# KickerBoard.net
KiCad netlist of a schematic drawn in EAGLE
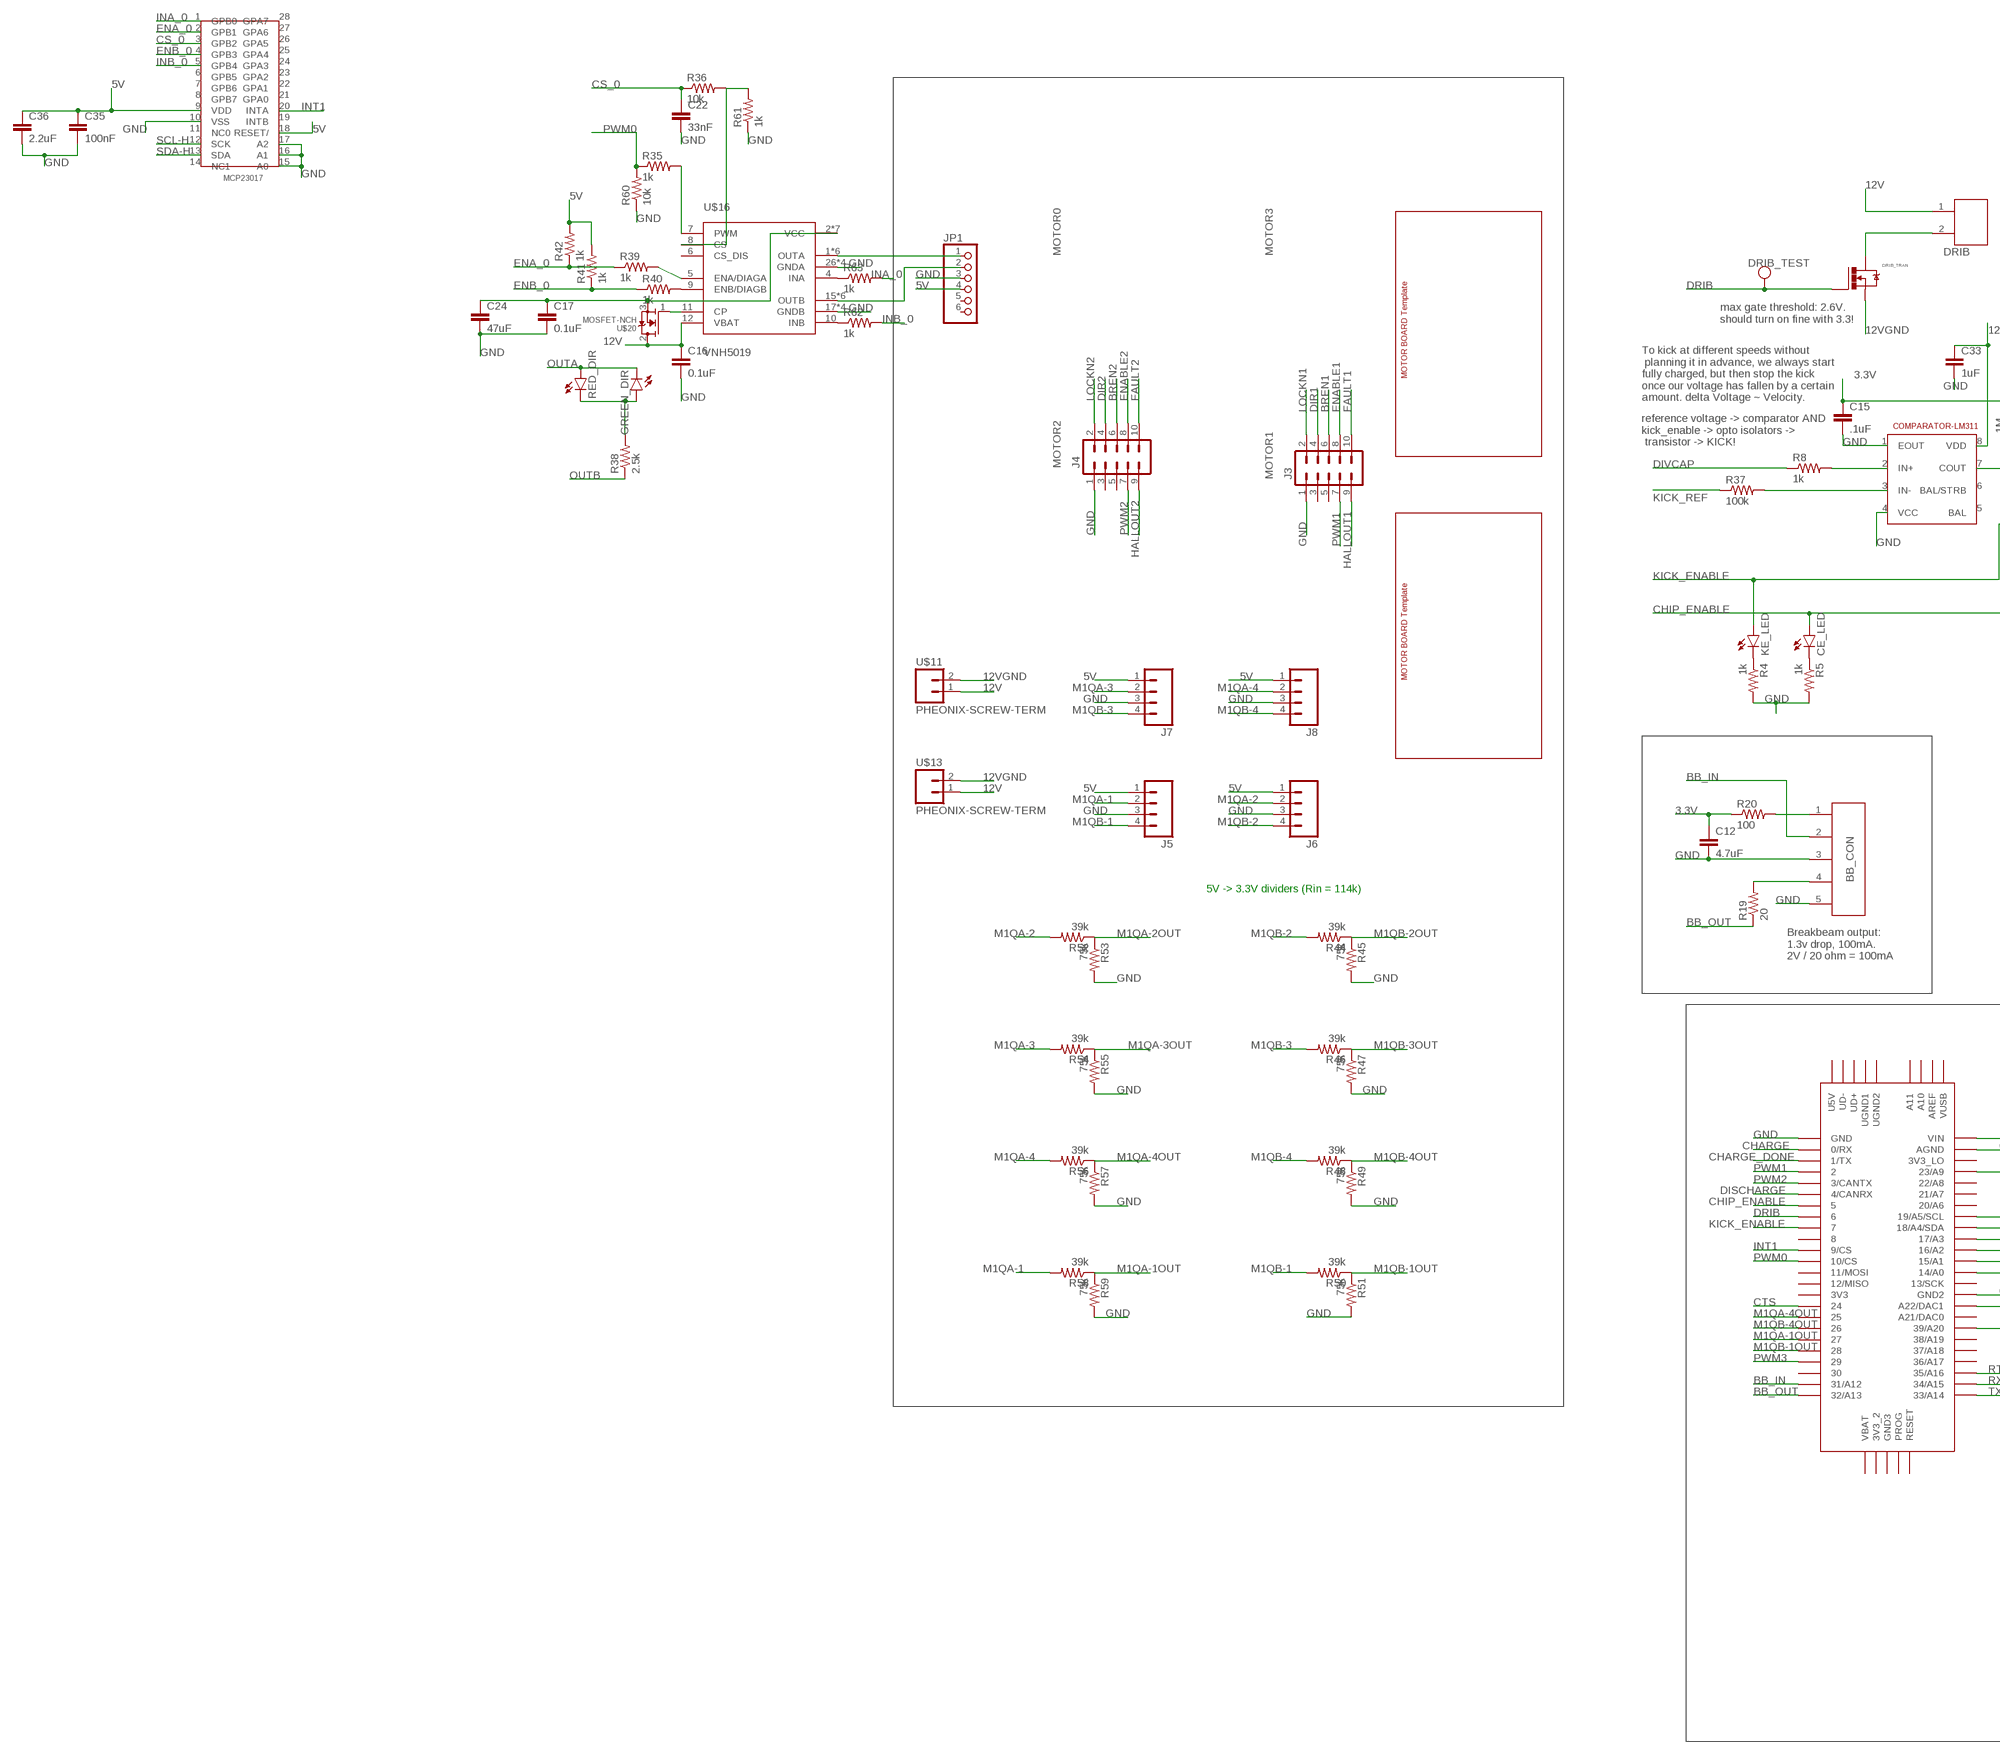
[diagram p0: schematic, sheet 1, part 1 of 2]
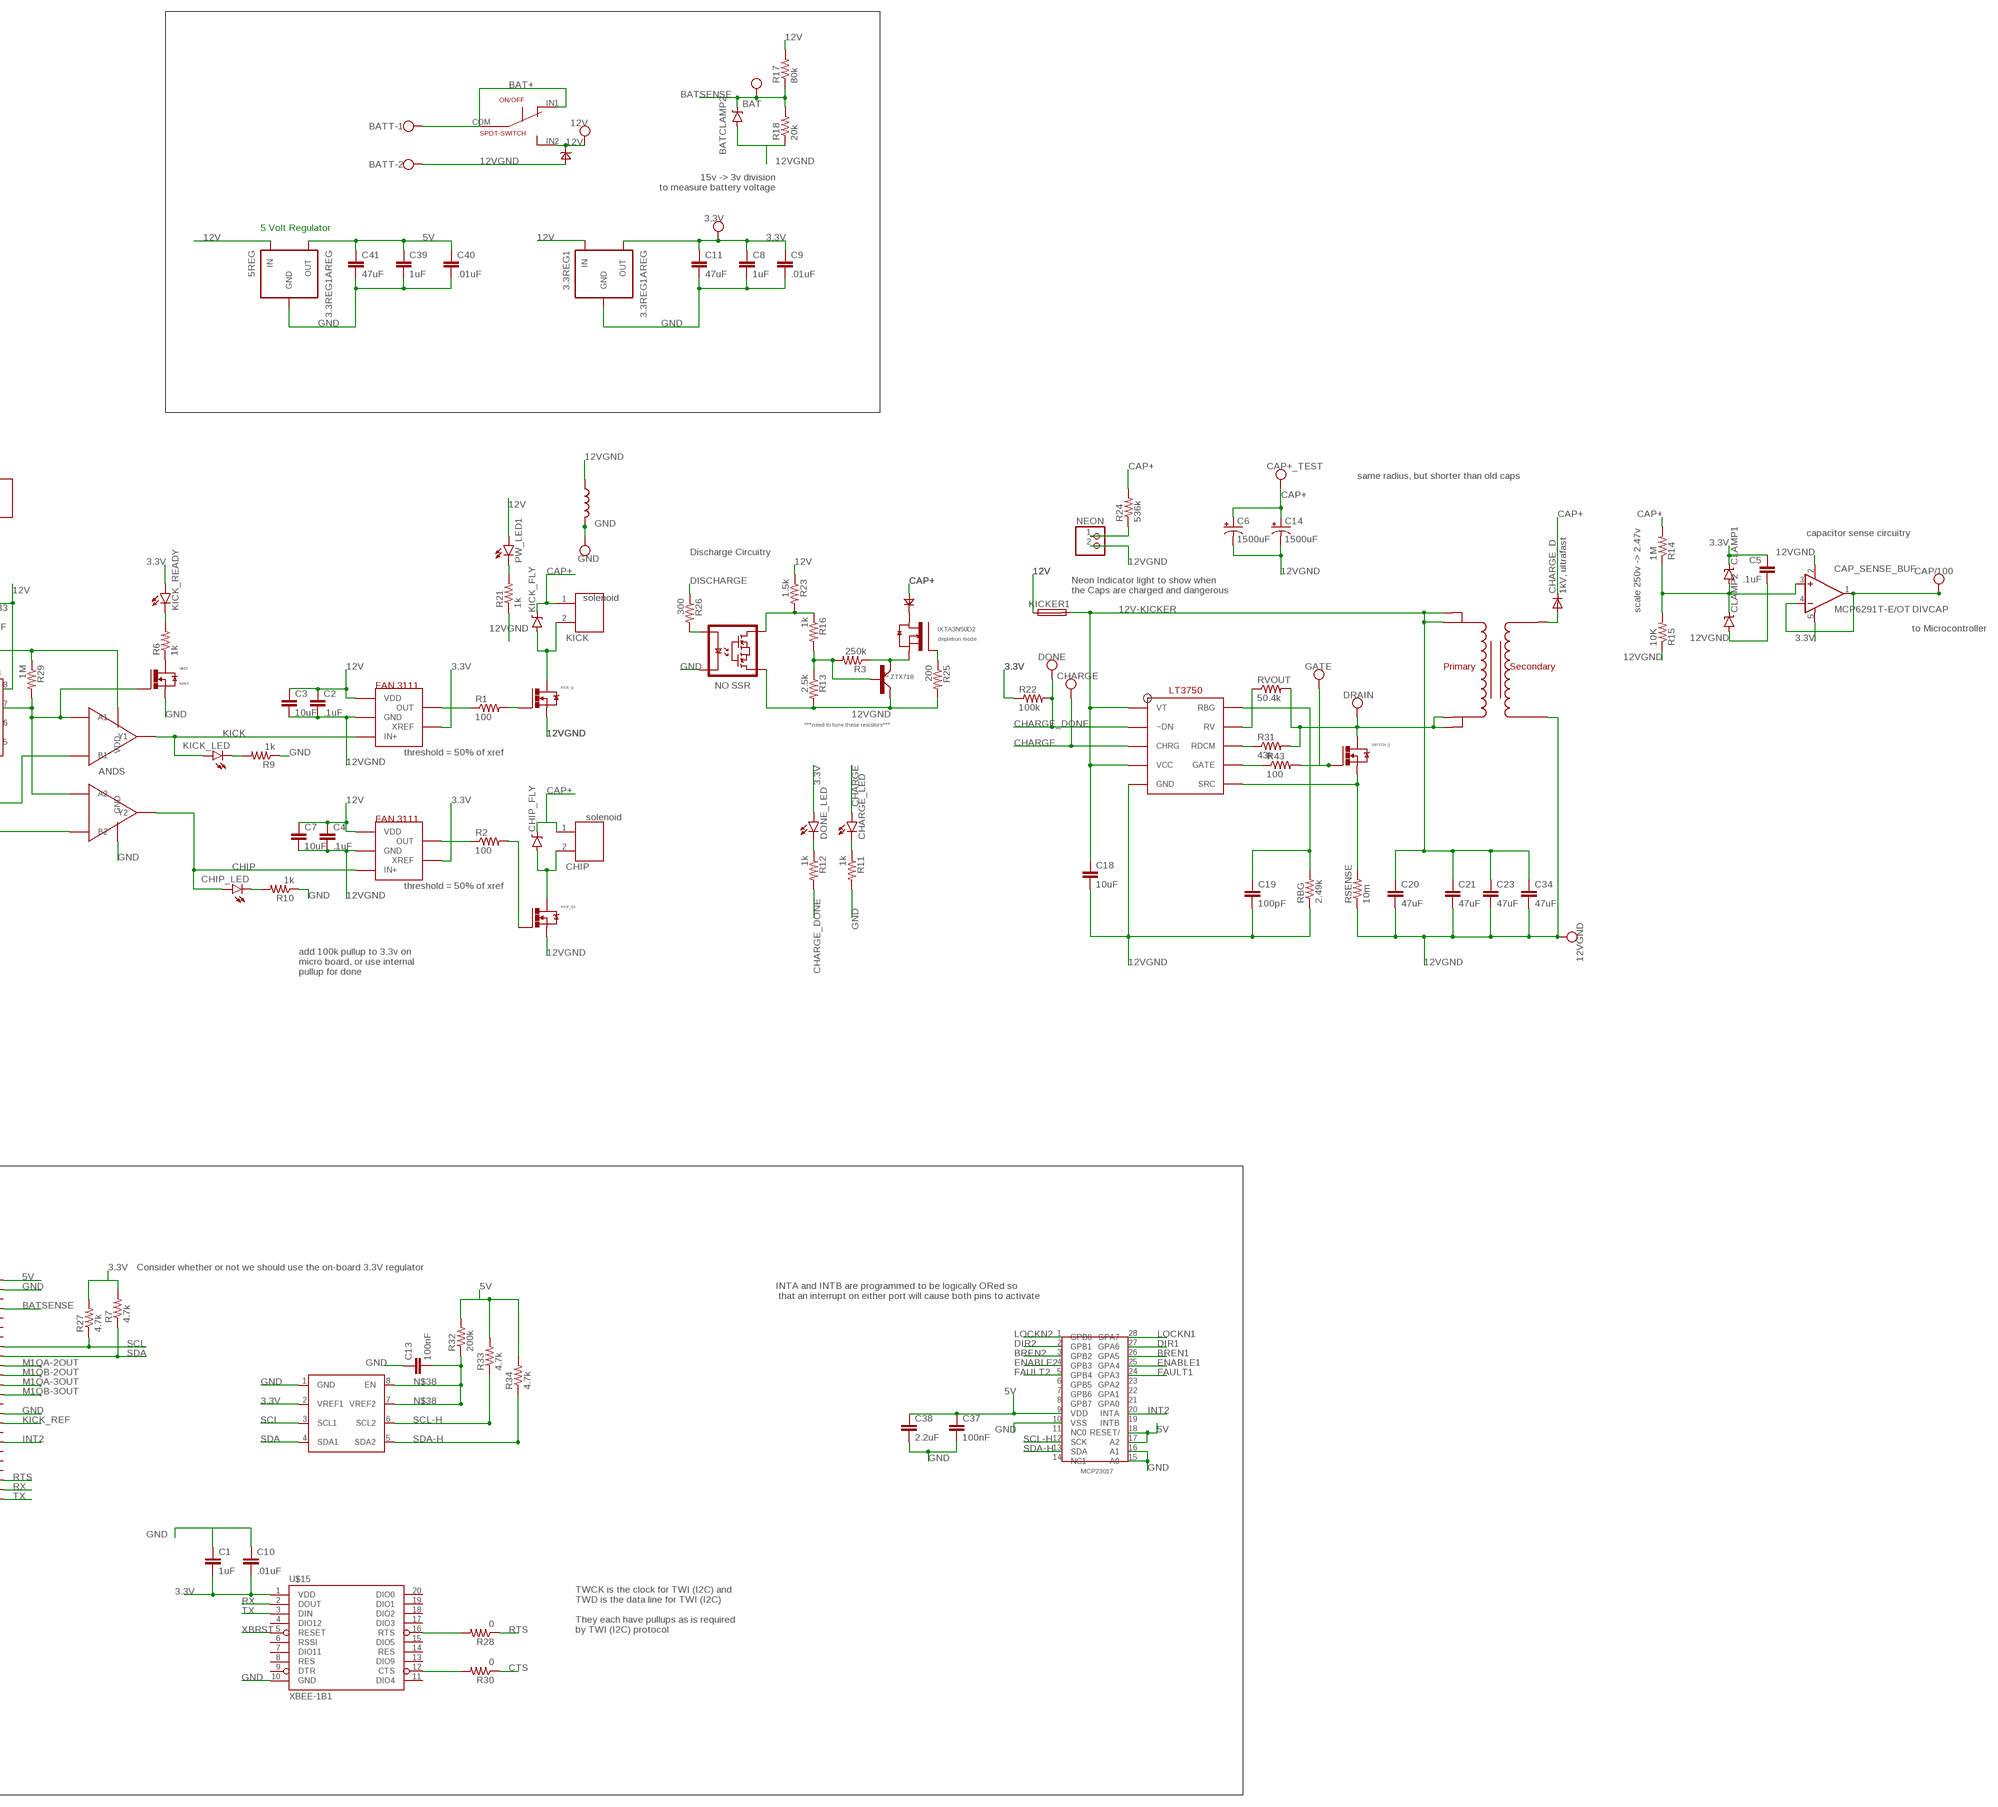
[diagram p1: schematic, sheet 1, part 2 of 2]

(export (version "E")
  (design (tool "Eeschema 10.0.6"))
  (components
    (comp (ref "3.3REG1")
      (value "3.3REG1AREG")
      (footprint "eagle-import:DPAK")
      (libsource (lib "eagle-import") (part "3.3REG1AREG"))
    )
    (comp (ref "3.3V")
      (value "TEST_PT")
      (footprint "eagle-import:TESTING_PT")
      (libsource (lib "eagle-import") (part "TEST_PT"))
    )
    (comp (ref "5REG")
      (value "3.3REG1AREG")
      (footprint "eagle-import:DPAK")
      (libsource (lib "eagle-import") (part "3.3REG1AREG"))
    )
    (comp (ref "12V")
      (value "TEST_PT")
      (footprint "eagle-import:TESTING_PT")
      (libsource (lib "eagle-import") (part "TEST_PT"))
    )
    (comp (ref "12VGND")
      (value "TEST_PT")
      (footprint "eagle-import:TESTING_PT")
      (libsource (lib "eagle-import") (part "TEST_PT"))
    )
    (comp (ref "ANDS")
      (value "AND-DUAL")
      (footprint "eagle-import:TSSOP8")
      (libsource (lib "eagle-import") (part "AND-DUAL"))
    )
    (comp (ref "BAT")
      (value "TEST_PT")
      (footprint "eagle-import:TESTING_PT")
      (libsource (lib "eagle-import") (part "TEST_PT"))
    )
    (comp (ref "BATCLAMP2")
      (value "DIODE-ZENERDO214AC")
      (footprint "eagle-import:DO214AC")
      (libsource (lib "eagle-import") (part "DIODE-ZENERDO214AC"))
    )
    (comp (ref "BATT")
      (value "W237-102")
      (footprint "eagle-import:W237-102")
      (fields (field (name "MPN") "237-102"))
      (libsource (lib "eagle-import") (part "W237-102"))
    )
    (comp (ref "BB_CON")
      (value "JST-5")
      (footprint "eagle-import:JST-5-2MM")
      (libsource (lib "eagle-import") (part "JST-5"))
    )
    (comp (ref "C1")
      (value "1uF")
      (footprint "eagle-import:1206")
      (libsource (lib "eagle-import") (part "CAP1206"))
    )
    (comp (ref "C2")
      (value ".1uF")
      (footprint "eagle-import:1206")
      (libsource (lib "eagle-import") (part "CAP1206"))
    )
    (comp (ref "C3")
      (value "10uF")
      (footprint "eagle-import:1206")
      (libsource (lib "eagle-import") (part "CAP1206"))
    )
    (comp (ref "C4")
      (value ".1uF")
      (footprint "eagle-import:1206")
      (libsource (lib "eagle-import") (part "CAP1206"))
    )
    (comp (ref "C5")
      (value ".1uF")
      (footprint "eagle-import:0805")
      (libsource (lib "eagle-import") (part "CAP0805"))
    )
    (comp (ref "C6")
      (value "1500uF")
      (footprint "eagle-import:EB35D")
      (libsource (lib "eagle-import") (part "CPOL-USE10-35"))
    )
    (comp (ref "C7")
      (value "10uF")
      (footprint "eagle-import:1206")
      (libsource (lib "eagle-import") (part "CAP1206"))
    )
    (comp (ref "C8")
      (value "1uF")
      (footprint "eagle-import:0805")
      (libsource (lib "eagle-import") (part "CAP0805"))
    )
    (comp (ref "C9")
      (value ".01uF")
      (footprint "eagle-import:0805")
      (libsource (lib "eagle-import") (part "CAP0805"))
    )
    (comp (ref "C10")
      (value ".01uF")
      (footprint "eagle-import:1206")
      (libsource (lib "eagle-import") (part "CAP1206"))
    )
    (comp (ref "C11")
      (value "47uF")
      (footprint "eagle-import:1206")
      (libsource (lib "eagle-import") (part "CAP1206"))
    )
    (comp (ref "C12")
      (value "4.7uF")
      (footprint "eagle-import:0805")
      (libsource (lib "eagle-import") (part "CAP0805"))
    )
    (comp (ref "C13")
      (value "100nF")
      (footprint "eagle-import:0805")
      (libsource (lib "eagle-import") (part "CAP0805"))
    )
    (comp (ref "C14")
      (value "1500uF")
      (footprint "eagle-import:EB35D")
      (libsource (lib "eagle-import") (part "CPOL-USE10-35"))
    )
    (comp (ref "C15")
      (value ".1uF")
      (footprint "eagle-import:0805")
      (libsource (lib "eagle-import") (part "CAP0805"))
    )
    (comp (ref "C16")
      (value "0.1uF")
      (footprint "eagle-import:0805")
      (libsource (lib "eagle-import") (part "CAP0805"))
    )
    (comp (ref "C17")
      (value "0.1uF")
      (footprint "eagle-import:0805")
      (libsource (lib "eagle-import") (part "CAP0805"))
    )
    (comp (ref "C18")
      (value "10uF")
      (footprint "eagle-import:0805")
      (libsource (lib "eagle-import") (part "CAP0805"))
    )
    (comp (ref "C19")
      (value "100pF")
      (footprint "eagle-import:0805")
      (libsource (lib "eagle-import") (part "CAP0805"))
    )
    (comp (ref "C20")
      (value "47uF")
      (footprint "eagle-import:1206")
      (libsource (lib "eagle-import") (part "CAP1206"))
    )
    (comp (ref "C21")
      (value "47uF")
      (footprint "eagle-import:1206")
      (libsource (lib "eagle-import") (part "CAP1206"))
    )
    (comp (ref "C22")
      (value "33nF")
      (footprint "eagle-import:0805")
      (libsource (lib "eagle-import") (part "CAP0805"))
    )
    (comp (ref "C23")
      (value "47uF")
      (footprint "eagle-import:1206")
      (libsource (lib "eagle-import") (part "CAP1206"))
    )
    (comp (ref "C24")
      (value "47uF")
      (footprint "eagle-import:1206")
      (libsource (lib "eagle-import") (part "CAP1206"))
    )
    (comp (ref "C33")
      (value "1uF")
      (footprint "eagle-import:1206")
      (libsource (lib "eagle-import") (part "CAP1206"))
    )
    (comp (ref "C34")
      (value "47uF")
      (footprint "eagle-import:1206")
      (libsource (lib "eagle-import") (part "CAP1206"))
    )
    (comp (ref "C35")
      (value "100nF")
      (footprint "eagle-import:0805")
      (libsource (lib "eagle-import") (part "CAP0805"))
    )
    (comp (ref "C36")
      (value "2.2uF")
      (footprint "eagle-import:0805")
      (libsource (lib "eagle-import") (part "CAP0805"))
    )
    (comp (ref "C37")
      (value "100nF")
      (footprint "eagle-import:0805")
      (libsource (lib "eagle-import") (part "CAP0805"))
    )
    (comp (ref "C38")
      (value "2.2uF")
      (footprint "eagle-import:0805")
      (libsource (lib "eagle-import") (part "CAP0805"))
    )
    (comp (ref "C39")
      (value "1uF")
      (footprint "eagle-import:0805")
      (libsource (lib "eagle-import") (part "CAP0805"))
    )
    (comp (ref "C40")
      (value ".01uF")
      (footprint "eagle-import:0805")
      (libsource (lib "eagle-import") (part "CAP0805"))
    )
    (comp (ref "C41")
      (value "47uF")
      (footprint "eagle-import:1206")
      (libsource (lib "eagle-import") (part "CAP1206"))
    )
    (comp (ref "CAP+_TEST")
      (value "TEST_PT")
      (footprint "eagle-import:TESTING_PT")
      (libsource (lib "eagle-import") (part "TEST_PT"))
    )
    (comp (ref "CAP/100")
      (value "TEST_PT")
      (footprint "eagle-import:TESTING_PT")
      (libsource (lib "eagle-import") (part "TEST_PT"))
    )
    (comp (ref "CAP_SENSE_BUF")
      (value "MCP6291T-E/OT")
      (footprint "eagle-import:SOT23-5")
      (libsource (lib "eagle-import") (part "MCP6291T-E/OT"))
    )
    (comp (ref "CE_LED")
      (value "LED1206")
      (footprint "eagle-import:LED-1206")
      (libsource (lib "eagle-import") (part "LED1206"))
    )
    (comp (ref "CHARGE")
      (value "TEST_PT")
      (footprint "eagle-import:TESTING_PT")
      (libsource (lib "eagle-import") (part "TEST_PT"))
    )
    (comp (ref "CHARGE_D")
      (value "1kV, ultrafast")
      (footprint "eagle-import:DO214AC")
      (libsource (lib "eagle-import") (part "DIODE-DO214AC"))
    )
    (comp (ref "CHARGE_LED")
      (value "LED1206")
      (footprint "eagle-import:LED-1206")
      (libsource (lib "eagle-import") (part "LED1206"))
    )
    (comp (ref "CHARGE_U")
      (value "LT3750")
      (footprint "eagle-import:10-MSOP")
      (libsource (lib "eagle-import") (part "LT3750"))
    )
    (comp (ref "CHIP")
      (value "JST-22MM")
      (footprint "eagle-import:JST-2-2MM")
      (libsource (lib "eagle-import") (part "JST-22MM"))
    )
    (comp (ref "CHIP_FLY")
      (value "DIODE-ZENERDO214AB")
      (footprint "eagle-import:DO214AB")
      (libsource (lib "eagle-import") (part "DIODE-ZENERDO214AB"))
    )
    (comp (ref "CHIP_LED")
      (value "LED1206")
      (footprint "eagle-import:LED-1206")
      (libsource (lib "eagle-import") (part "LED1206"))
    )
    (comp (ref "CLAMP1")
      (value "DIODE-ZENERDO214AC")
      (footprint "eagle-import:DO214AC")
      (libsource (lib "eagle-import") (part "DIODE-ZENERDO214AC"))
    )
    (comp (ref "CLAMP2")
      (value "DIODE-ZENERDO214AC")
      (footprint "eagle-import:DO214AC")
      (libsource (lib "eagle-import") (part "DIODE-ZENERDO214AC"))
    )
    (comp (ref "DONE")
      (value "TEST_PT")
      (footprint "eagle-import:TESTING_PT")
      (libsource (lib "eagle-import") (part "TEST_PT"))
    )
    (comp (ref "DONE_LED")
      (value "LED1206")
      (footprint "eagle-import:LED-1206")
      (libsource (lib "eagle-import") (part "LED1206"))
    )
    (comp (ref "DRAIN")
      (value "TEST_PT")
      (footprint "eagle-import:TESTING_PT")
      (libsource (lib "eagle-import") (part "TEST_PT"))
    )
    (comp (ref "DRIB")
      (value "JST-22MM")
      (footprint "eagle-import:JST-2-2MM")
      (libsource (lib "eagle-import") (part "JST-22MM"))
    )
    (comp (ref "DRIB_TEST")
      (value "TEST_PT")
      (footprint "eagle-import:TESTING_PT")
      (libsource (lib "eagle-import") (part "TEST_PT"))
    )
    (comp (ref "DRIB_TRAN")
      (value "N-MOSFETDPAK")
      (footprint "eagle-import:DPAK")
      (libsource (lib "eagle-import") (part "N-MOSFETDPAK"))
    )
    (comp (ref "GATE")
      (value "TEST_PT")
      (footprint "eagle-import:TESTING_PT")
      (libsource (lib "eagle-import") (part "TEST_PT"))
    )
    (comp (ref "GND")
      (value "TEST_PT")
      (footprint "eagle-import:TESTING_PT")
      (libsource (lib "eagle-import") (part "TEST_PT"))
    )
    (comp (ref "GREEN_DIR")
      (value "LED1206")
      (footprint "eagle-import:LED-1206")
      (libsource (lib "eagle-import") (part "LED1206"))
    )
    (comp (ref "J3")
      (value "M05X2SHD")
      (footprint "eagle-import:2X5-SHROUDED")
      (libsource (lib "eagle-import") (part "M05X2SHD"))
    )
    (comp (ref "J4")
      (value "M05X2SHD")
      (footprint "eagle-import:2X5-SHROUDED")
      (libsource (lib "eagle-import") (part "M05X2SHD"))
    )
    (comp (ref "J5")
      (value "M04PTH")
      (footprint "eagle-import:1X04")
      (libsource (lib "eagle-import") (part "M04PTH"))
    )
    (comp (ref "J6")
      (value "M04PTH")
      (footprint "eagle-import:1X04")
      (libsource (lib "eagle-import") (part "M04PTH"))
    )
    (comp (ref "J7")
      (value "M04PTH")
      (footprint "eagle-import:1X04")
      (libsource (lib "eagle-import") (part "M04PTH"))
    )
    (comp (ref "J8")
      (value "M04PTH")
      (footprint "eagle-import:1X04")
      (libsource (lib "eagle-import") (part "M04PTH"))
    )
    (comp (ref "JP1")
      (value "PINHD-1X6")
      (footprint "eagle-import:1X06")
      (libsource (lib "eagle-import") (part "PINHD-1X6"))
    )
    (comp (ref "KE_LED")
      (value "LED1206")
      (footprint "eagle-import:LED-1206")
      (libsource (lib "eagle-import") (part "LED1206"))
    )
    (comp (ref "KICK")
      (value "JST-22MM")
      (footprint "eagle-import:JST-2-2MM")
      (libsource (lib "eagle-import") (part "JST-22MM"))
    )
    (comp (ref "KICKER1")
      (value "TR5")
      (footprint "eagle-import:TR5")
      (libsource (lib "eagle-import") (part "TR5"))
    )
    (comp (ref "KICK_FLY")
      (value "DIODE-ZENERDO214AB")
      (footprint "eagle-import:DO214AB")
      (libsource (lib "eagle-import") (part "DIODE-ZENERDO214AB"))
    )
    (comp (ref "KICK_LED")
      (value "LED1206")
      (footprint "eagle-import:LED-1206")
      (libsource (lib "eagle-import") (part "LED1206"))
    )
    (comp (ref "KICK_Q")
      (value "N-MOSFETDPAK")
      (footprint "eagle-import:DPAK")
      (libsource (lib "eagle-import") (part "N-MOSFETDPAK"))
    )
    (comp (ref "KICK_Q1")
      (value "N-MOSFETDPAK")
      (footprint "eagle-import:DPAK")
      (libsource (lib "eagle-import") (part "N-MOSFETDPAK"))
    )
    (comp (ref "KICK_READY")
      (value "LED1206")
      (footprint "eagle-import:LED-1206")
      (libsource (lib "eagle-import") (part "LED1206"))
    )
    (comp (ref "NEON")
      (value "PINHD-1X2")
      (footprint "eagle-import:1X02")
      (libsource (lib "eagle-import") (part "PINHD-1X2"))
    )
    (comp (ref "ON/OFF")
      (value "SPDT-SWITCH")
      (footprint "eagle-import:CK_SWITCH")
      (libsource (lib "eagle-import") (part "SPDT-SWITCH"))
    )
    (comp (ref "PW_LED1")
      (value "LED1206")
      (footprint "eagle-import:LED-1206")
      (libsource (lib "eagle-import") (part "LED1206"))
    )
    (comp (ref "R1")
      (value "100")
      (footprint "eagle-import:0805")
      (libsource (lib "eagle-import") (part "SparkFun-Resistors_RESISTOR0805-RES"))
    )
    (comp (ref "R2")
      (value "100")
      (footprint "eagle-import:0805")
      (libsource (lib "eagle-import") (part "SparkFun-Resistors_RESISTOR0805-RES"))
    )
    (comp (ref "R3")
      (value "250k")
      (footprint "eagle-import:0805")
      (libsource (lib "eagle-import") (part "RESISTOR0805-RES"))
    )
    (comp (ref "R4")
      (value "1k")
      (footprint "eagle-import:0805")
      (libsource (lib "eagle-import") (part "RESISTOR0805-RES"))
    )
    (comp (ref "R5")
      (value "1k")
      (footprint "eagle-import:0805")
      (libsource (lib "eagle-import") (part "RESISTOR0805-RES"))
    )
    (comp (ref "R6")
      (value "1k")
      (footprint "eagle-import:0805")
      (libsource (lib "eagle-import") (part "RESISTOR0805-RES"))
    )
    (comp (ref "R7")
      (value "4.7k")
      (footprint "eagle-import:0805")
      (libsource (lib "eagle-import") (part "SparkFun-Resistors_RESISTOR0805-RES"))
    )
    (comp (ref "R8")
      (value "1k")
      (footprint "eagle-import:0805")
      (libsource (lib "eagle-import") (part "RESISTOR0805-RES"))
    )
    (comp (ref "R9")
      (value "1k")
      (footprint "eagle-import:0805")
      (libsource (lib "eagle-import") (part "RESISTOR0805-RES"))
    )
    (comp (ref "R10")
      (value "1k")
      (footprint "eagle-import:0805")
      (libsource (lib "eagle-import") (part "RESISTOR0805-RES"))
    )
    (comp (ref "R11")
      (value "1k")
      (footprint "eagle-import:0805")
      (libsource (lib "eagle-import") (part "RESISTOR0805-RES"))
    )
    (comp (ref "R12")
      (value "1k")
      (footprint "eagle-import:0805")
      (libsource (lib "eagle-import") (part "RESISTOR0805-RES"))
    )
    (comp (ref "R13")
      (value "2.5k")
      (footprint "eagle-import:0805")
      (libsource (lib "eagle-import") (part "RESISTOR0805-RES"))
    )
    (comp (ref "R14")
      (value "1M")
      (footprint "eagle-import:0805")
      (libsource (lib "eagle-import") (part "SparkFun-Resistors_RESISTOR0805-RES"))
    )
    (comp (ref "R15")
      (value "10K")
      (footprint "eagle-import:0805")
      (libsource (lib "eagle-import") (part "SparkFun-Resistors_RESISTOR0805-RES"))
    )
    (comp (ref "R16")
      (value "1k")
      (footprint "eagle-import:0805")
      (libsource (lib "eagle-import") (part "RESISTOR0805-RES"))
    )
    (comp (ref "R17")
      (value "80k")
      (footprint "eagle-import:0805")
      (libsource (lib "eagle-import") (part "RESISTOR0805-RES"))
    )
    (comp (ref "R18")
      (value "20k")
      (footprint "eagle-import:0805")
      (libsource (lib "eagle-import") (part "RESISTOR0805-RES"))
    )
    (comp (ref "R19")
      (value "20")
      (footprint "eagle-import:0805")
      (libsource (lib "eagle-import") (part "RESISTOR0805-RES"))
    )
    (comp (ref "R20")
      (value "100")
      (footprint "eagle-import:0805")
      (libsource (lib "eagle-import") (part "RESISTOR0805-RES"))
    )
    (comp (ref "R21")
      (value "1k")
      (footprint "eagle-import:0805")
      (libsource (lib "eagle-import") (part "RESISTOR0805-RES"))
    )
    (comp (ref "R22")
      (value "100k")
      (footprint "eagle-import:0805")
      (libsource (lib "eagle-import") (part "RESISTOR0805-RES"))
    )
    (comp (ref "R23")
      (value "1.5k")
      (footprint "eagle-import:0805")
      (libsource (lib "eagle-import") (part "RESISTOR0805-RES"))
    )
    (comp (ref "R24")
      (value "536k")
      (footprint "eagle-import:0805")
      (libsource (lib "eagle-import") (part "RESISTOR0805-RES"))
    )
    (comp (ref "R25")
      (value "200")
      (footprint "eagle-import:0805")
      (libsource (lib "eagle-import") (part "RESISTOR0805-RES"))
    )
    (comp (ref "R26")
      (value "300")
      (footprint "eagle-import:0805")
      (libsource (lib "eagle-import") (part "RESISTOR0805-RES"))
    )
    (comp (ref "R27")
      (value "4.7k")
      (footprint "eagle-import:0805")
      (libsource (lib "eagle-import") (part "SparkFun-Resistors_RESISTOR0805-RES"))
    )
    (comp (ref "R28")
      (value "0")
      (footprint "eagle-import:0805")
      (libsource (lib "eagle-import") (part "SparkFun-Resistors_RESISTOR0805-RES"))
    )
    (comp (ref "R29")
      (value "1M")
      (footprint "eagle-import:0805")
      (libsource (lib "eagle-import") (part "RESISTOR0805-RES"))
    )
    (comp (ref "R30")
      (value "0")
      (footprint "eagle-import:0805")
      (libsource (lib "eagle-import") (part "SparkFun-Resistors_RESISTOR0805-RES"))
    )
    (comp (ref "R31")
      (value "43k")
      (footprint "eagle-import:0805")
      (libsource (lib "eagle-import") (part "RESISTOR0805-RES"))
    )
    (comp (ref "R32")
      (value "200k")
      (footprint "eagle-import:0805")
      (libsource (lib "eagle-import") (part "SparkFun-Resistors_RESISTOR0805-RES"))
    )
    (comp (ref "R33")
      (value "4.7k")
      (footprint "eagle-import:0805")
      (libsource (lib "eagle-import") (part "SparkFun-Resistors_RESISTOR0805-RES"))
    )
    (comp (ref "R34")
      (value "4.7k")
      (footprint "eagle-import:0805")
      (libsource (lib "eagle-import") (part "SparkFun-Resistors_RESISTOR0805-RES"))
    )
    (comp (ref "R35")
      (value "1k")
      (footprint "eagle-import:0805")
      (libsource (lib "eagle-import") (part "RESISTOR0805-RES"))
    )
    (comp (ref "R36")
      (value "10k")
      (footprint "eagle-import:0805")
      (libsource (lib "eagle-import") (part "RESISTOR0805-RES"))
    )
    (comp (ref "R37")
      (value "100k")
      (footprint "eagle-import:0805")
      (libsource (lib "eagle-import") (part "RESISTOR0805-RES"))
    )
    (comp (ref "R38")
      (value "2.5k")
      (footprint "eagle-import:0805")
      (libsource (lib "eagle-import") (part "RESISTOR0805-RES"))
    )
    (comp (ref "R39")
      (value "1k")
      (footprint "eagle-import:0805")
      (libsource (lib "eagle-import") (part "RESISTOR0805-RES"))
    )
    (comp (ref "R40")
      (value "1k")
      (footprint "eagle-import:0805")
      (libsource (lib "eagle-import") (part "RESISTOR0805-RES"))
    )
    (comp (ref "R41")
      (value "1k")
      (footprint "eagle-import:0805")
      (libsource (lib "eagle-import") (part "RESISTOR0805-RES"))
    )
    (comp (ref "R42")
      (value "1k")
      (footprint "eagle-import:0805")
      (libsource (lib "eagle-import") (part "RESISTOR0805-RES"))
    )
    (comp (ref "R43")
      (value "100")
      (footprint "eagle-import:0805")
      (libsource (lib "eagle-import") (part "RESISTOR0805-RES"))
    )
    (comp (ref "R44")
      (value "39k")
      (footprint "eagle-import:0805")
      (libsource (lib "eagle-import") (part "RESISTOR0805-RES"))
    )
    (comp (ref "R45")
      (value "75k")
      (footprint "eagle-import:0805")
      (libsource (lib "eagle-import") (part "RESISTOR0805-RES"))
    )
    (comp (ref "R46")
      (value "39k")
      (footprint "eagle-import:0805")
      (libsource (lib "eagle-import") (part "RESISTOR0805-RES"))
    )
    (comp (ref "R47")
      (value "75k")
      (footprint "eagle-import:0805")
      (libsource (lib "eagle-import") (part "RESISTOR0805-RES"))
    )
    (comp (ref "R48")
      (value "39k")
      (footprint "eagle-import:0805")
      (libsource (lib "eagle-import") (part "RESISTOR0805-RES"))
    )
    (comp (ref "R49")
      (value "75k")
      (footprint "eagle-import:0805")
      (libsource (lib "eagle-import") (part "RESISTOR0805-RES"))
    )
    (comp (ref "R50")
      (value "39k")
      (footprint "eagle-import:0805")
      (libsource (lib "eagle-import") (part "RESISTOR0805-RES"))
    )
    (comp (ref "R51")
      (value "75k")
      (footprint "eagle-import:0805")
      (libsource (lib "eagle-import") (part "RESISTOR0805-RES"))
    )
    (comp (ref "R52")
      (value "39k")
      (footprint "eagle-import:0805")
      (libsource (lib "eagle-import") (part "RESISTOR0805-RES"))
    )
    (comp (ref "R53")
      (value "75k")
      (footprint "eagle-import:0805")
      (libsource (lib "eagle-import") (part "RESISTOR0805-RES"))
    )
    (comp (ref "R54")
      (value "39k")
      (footprint "eagle-import:0805")
      (libsource (lib "eagle-import") (part "RESISTOR0805-RES"))
    )
    (comp (ref "R55")
      (value "75k")
      (footprint "eagle-import:0805")
      (libsource (lib "eagle-import") (part "RESISTOR0805-RES"))
    )
    (comp (ref "R56")
      (value "39k")
      (footprint "eagle-import:0805")
      (libsource (lib "eagle-import") (part "RESISTOR0805-RES"))
    )
    (comp (ref "R57")
      (value "75k")
      (footprint "eagle-import:0805")
      (libsource (lib "eagle-import") (part "RESISTOR0805-RES"))
    )
    (comp (ref "R58")
      (value "39k")
      (footprint "eagle-import:0805")
      (libsource (lib "eagle-import") (part "RESISTOR0805-RES"))
    )
    (comp (ref "R59")
      (value "75k")
      (footprint "eagle-import:0805")
      (libsource (lib "eagle-import") (part "RESISTOR0805-RES"))
    )
    (comp (ref "R60")
      (value "10k")
      (footprint "eagle-import:0805")
      (libsource (lib "eagle-import") (part "RESISTOR0805-RES"))
    )
    (comp (ref "R61")
      (value "1k")
      (footprint "eagle-import:0805")
      (libsource (lib "eagle-import") (part "RESISTOR0805-RES"))
    )
    (comp (ref "R62")
      (value "1k")
      (footprint "eagle-import:0805")
      (libsource (lib "eagle-import") (part "RESISTOR0805-RES"))
    )
    (comp (ref "R63")
      (value "1k")
      (footprint "eagle-import:0805")
      (libsource (lib "eagle-import") (part "RESISTOR0805-RES"))
    )
    (comp (ref "RBG")
      (value "2.49k")
      (footprint "eagle-import:0805")
      (libsource (lib "eagle-import") (part "RESISTOR0805-RES"))
    )
    (comp (ref "RED_DIR")
      (value "LED1206")
      (footprint "eagle-import:LED-1206")
      (libsource (lib "eagle-import") (part "LED1206"))
    )
    (comp (ref "RSENSE")
      (value "10m")
      (footprint "eagle-import:R2512")
      (libsource (lib "eagle-import") (part "RESISTOR2512"))
    )
    (comp (ref "RVOUT")
      (value "50.4k")
      (footprint "eagle-import:0805")
      (libsource (lib "eagle-import") (part "RESISTOR0805-RES"))
    )
    (comp (ref "SWITCH_Q")
      (value "N-MOSFETDPAK")
      (footprint "eagle-import:DPAK")
      (libsource (lib "eagle-import") (part "N-MOSFETDPAK"))
    )
    (comp (ref "U$1")
      (value "FAN31111")
      (footprint "eagle-import:SOT23-5")
      (libsource (lib "eagle-import") (part "FAN31111"))
    )
    (comp (ref "U$2")
      (value "IXTA3N50D2")
      (footprint "eagle-import:TO-263")
      (libsource (lib "eagle-import") (part "IXTA3N50D2"))
    )
    (comp (ref "U$3")
      (value "32052-TRANSFORMER")
      (footprint "eagle-import:10-TRANSFORMER")
      (libsource (lib "eagle-import") (part "32052-TRANSFORMER"))
    )
    (comp (ref "U$4")
      (value "FAN31111")
      (footprint "eagle-import:SOT23-5")
      (libsource (lib "eagle-import") (part "FAN31111"))
    )
    (comp (ref "U$5")
      (value "VO1400AEFTR")
      (footprint "eagle-import:SOP4")
      (libsource (lib "eagle-import") (part "VO1400AEFTR"))
    )
    (comp (ref "U$6")
      (value "ZTX718")
      (footprint "eagle-import:TO92")
      (libsource (lib "eagle-import") (part "ZTX718"))
    )
    (comp (ref "U$7")
      (value "1N4007")
      (footprint "eagle-import:THROUGH-HOLE-2")
      (libsource (lib "eagle-import") (part "1N4007"))
    )
    (comp (ref "U$8")
      (value "PCA9306")
      (footprint "eagle-import:SOIC8")
      (libsource (lib "eagle-import") (part "PCA9306"))
    )
    (comp (ref "U$9")
      (value "MOTOR_BOARD")
      (footprint "eagle-import:MOTOR_BOARD")
      (libsource (lib "eagle-import") (part "MOTOR_BOARD"))
    )
    (comp (ref "U$10")
      (value "MOTOR_BOARD")
      (footprint "eagle-import:MOTOR_BOARD")
      (libsource (lib "eagle-import") (part "MOTOR_BOARD"))
    )
    (comp (ref "U$11")
      (value "PHEONIX-SCREW-TERM")
      (footprint "eagle-import:1X02-PHEONIX")
      (libsource (lib "eagle-import") (part "PHEONIX-SCREW-TERM"))
    )
    (comp (ref "U$12")
      (value "13VZENER")
      (footprint "eagle-import:THROUGH-HOLE-2")
      (libsource (lib "eagle-import") (part "13VZENER"))
    )
    (comp (ref "U$13")
      (value "PHEONIX-SCREW-TERM")
      (footprint "eagle-import:1X02-PHEONIX")
      (libsource (lib "eagle-import") (part "PHEONIX-SCREW-TERM"))
    )
    (comp (ref "U$14")
      (value "TEENSY_3.5/3.6")
      (footprint "eagle-import:TEENSY_3.5_3.6")
      (libsource (lib "eagle-import") (part "TEENSY_3.5/3.6"))
    )
    (comp (ref "U$15")
      (value "XBEE-1B1")
      (footprint "eagle-import:XBEE-1")
      (libsource (lib "eagle-import") (part "XBEE-1B1"))
    )
    (comp (ref "U$16")
      (value "VNH5019")
      (footprint "eagle-import:MULTIPOWERSO-30")
      (libsource (lib "eagle-import") (part "VNH5019"))
    )
    (comp (ref "U$17")
      (value "IO-EXPANDER")
      (footprint "eagle-import:SSOP")
      (libsource (lib "eagle-import") (part "IO-EXPANDER"))
    )
    (comp (ref "U$18")
      (value "LM311")
      (footprint "eagle-import:SOIC8")
      (libsource (lib "eagle-import") (part "LM311"))
    )
    (comp (ref "U$19")
      (value "INDUCTOR")
      (footprint "eagle-import:0805")
      (libsource (lib "eagle-import") (part "INDUCTOR"))
    )
    (comp (ref "U$20")
      (value "MOSFET-NCH")
      (footprint "eagle-import:TO252-3")
      (libsource (lib "eagle-import") (part "MOSFET-NCH"))
    )
    (comp (ref "U$21")
      (value "IO-EXPANDER")
      (footprint "eagle-import:SSOP")
      (libsource (lib "eagle-import") (part "IO-EXPANDER"))
    )
    (comp (ref "U$22")
      (value "N-FET")
      (footprint "eagle-import:SOT-23")
      (libsource (lib "eagle-import") (part "N-FET"))
    )
  )
  (nets
    (net (code "1") (name "/3.3V") (class "Default")
      (node (ref "3.3REG1") (pin "SOURCE") (pinfunction "OUT_SOURCE") (pintype "bidirectional"))
      (node (ref "3.3V") (pin "P$1") (pinfunction "P$1_P$1") (pintype "bidirectional"))
      (node (ref "ANDS") (pin "P$8") (pinfunction "VDD_P$8") (pintype "bidirectional"))
      (node (ref "C1") (pin "2") (pinfunction "2_2") (pintype "passive"))
      (node (ref "C10") (pin "2") (pinfunction "2_2") (pintype "passive"))
      (node (ref "C11") (pin "1") (pinfunction "1_1") (pintype "passive"))
      (node (ref "C12") (pin "1") (pinfunction "1_1") (pintype "passive"))
      (node (ref "C15") (pin "1") (pinfunction "1_1") (pintype "passive"))
      (node (ref "C5") (pin "1") (pinfunction "1_1") (pintype "passive"))
      (node (ref "C8") (pin "1") (pinfunction "1_1") (pintype "passive"))
      (node (ref "C9") (pin "1") (pinfunction "1_1") (pintype "passive"))
      (node (ref "CAP_SENSE_BUF") (pin "5") (pinfunction "V+_5") (pintype "power_in"))
      (node (ref "CLAMP1") (pin "C") (pinfunction "C_C") (pintype "passive"))
      (node (ref "DONE_LED") (pin "A") (pinfunction "A_A") (pintype "passive"))
      (node (ref "KICK_READY") (pin "A") (pinfunction "A_A") (pintype "passive"))
      (node (ref "R20") (pin "1") (pinfunction "1_1") (pintype "passive"))
      (node (ref "R22") (pin "1") (pinfunction "1_1") (pintype "passive"))
      (node (ref "R27") (pin "2") (pinfunction "2_2") (pintype "passive"))
      (node (ref "R29") (pin "1") (pinfunction "1_1") (pintype "passive"))
      (node (ref "R7") (pin "2") (pinfunction "2_2") (pintype "passive"))
      (node (ref "U$1") (pin "4") (pinfunction "XREF_4") (pintype "input"))
      (node (ref "U$15") (pin "1") (pinfunction "VDD_1") (pintype "power_in"))
      (node (ref "U$4") (pin "4") (pinfunction "XREF_4") (pintype "input"))
      (node (ref "U$8") (pin "2") (pinfunction "VREF1_2") (pintype "bidirectional"))
    )
    (net (code "2") (name "/5V") (class "Default")
      (node (ref "5REG") (pin "SOURCE") (pinfunction "OUT_SOURCE") (pintype "bidirectional"))
      (node (ref "C35") (pin "1") (pinfunction "1_1") (pintype "passive"))
      (node (ref "C36") (pin "1") (pinfunction "1_1") (pintype "passive"))
      (node (ref "C37") (pin "1") (pinfunction "1_1") (pintype "passive"))
      (node (ref "C38") (pin "1") (pinfunction "1_1") (pintype "passive"))
      (node (ref "C39") (pin "1") (pinfunction "1_1") (pintype "passive"))
      (node (ref "C40") (pin "1") (pinfunction "1_1") (pintype "passive"))
      (node (ref "C41") (pin "1") (pinfunction "1_1") (pintype "passive"))
      (node (ref "J5") (pin "1") (pinfunction "1_1") (pintype "passive"))
      (node (ref "J6") (pin "1") (pinfunction "1_1") (pintype "passive"))
      (node (ref "J7") (pin "1") (pinfunction "1_1") (pintype "passive"))
      (node (ref "J8") (pin "1") (pinfunction "1_1") (pintype "passive"))
      (node (ref "JP1") (pin "4") (pinfunction "4_4") (pintype "passive"))
      (node (ref "R32") (pin "2") (pinfunction "2_2") (pintype "passive"))
      (node (ref "R33") (pin "2") (pinfunction "2_2") (pintype "passive"))
      (node (ref "R34") (pin "2") (pinfunction "2_2") (pintype "passive"))
      (node (ref "R41") (pin "2") (pinfunction "2_2") (pintype "passive"))
      (node (ref "R42") (pin "2") (pinfunction "2_2") (pintype "passive"))
      (node (ref "U$14") (pin "VIN") (pinfunction "VIN_VIN") (pintype "bidirectional"))
      (node (ref "U$17") (pin "18") (pinfunction "RESET/_18") (pintype "bidirectional"))
      (node (ref "U$17") (pin "9") (pinfunction "VDD_9") (pintype "bidirectional"))
      (node (ref "U$21") (pin "17") (pinfunction "A2_17") (pintype "bidirectional"))
      (node (ref "U$21") (pin "18") (pinfunction "RESET/_18") (pintype "bidirectional"))
      (node (ref "U$21") (pin "9") (pinfunction "VDD_9") (pintype "bidirectional"))
    )
    (net (code "3") (name "/12V") (class "Default")
      (node (ref "12V") (pin "P$1") (pinfunction "P$1_P$1") (pintype "bidirectional"))
      (node (ref "3.3REG1") (pin "GATE") (pinfunction "IN_GATE") (pintype "input"))
      (node (ref "5REG") (pin "GATE") (pinfunction "IN_GATE") (pintype "input"))
      (node (ref "C16") (pin "1") (pinfunction "1_1") (pintype "passive"))
      (node (ref "C2") (pin "1") (pinfunction "1_1") (pintype "passive"))
      (node (ref "C3") (pin "1") (pinfunction "1_1") (pintype "passive"))
      (node (ref "C33") (pin "1") (pinfunction "1_1") (pintype "passive"))
      (node (ref "C4") (pin "1") (pinfunction "1_1") (pintype "passive"))
      (node (ref "C7") (pin "1") (pinfunction "1_1") (pintype "passive"))
      (node (ref "DRIB") (pin "1") (pinfunction "P$1_1") (pintype "bidirectional"))
      (node (ref "KICKER1") (pin "1") (pinfunction "1_1") (pintype "passive"))
      (node (ref "ON/OFF") (pin "IN2") (pinfunction "P2_IN2") (pintype "bidirectional"))
      (node (ref "PW_LED1") (pin "A") (pinfunction "A_A") (pintype "passive"))
      (node (ref "R17") (pin "2") (pinfunction "2_2") (pintype "passive"))
      (node (ref "R23") (pin "1") (pinfunction "1_1") (pintype "passive"))
      (node (ref "U$1") (pin "1") (pinfunction "VDD_1") (pintype "power_in"))
      (node (ref "U$11") (pin "1") (pinfunction "1_1") (pintype "passive"))
      (node (ref "U$12") (pin "-") (pinfunction "-_-") (pintype "bidirectional"))
      (node (ref "U$13") (pin "1") (pinfunction "1_1") (pintype "passive"))
      (node (ref "U$16") (pin "12") (pinfunction "VBAT_12") (pintype "bidirectional"))
      (node (ref "U$18") (pin "8") (pinfunction "VDD_8") (pintype "bidirectional"))
      (node (ref "U$20") (pin "2") (pinfunction "D_2") (pintype "bidirectional"))
      (node (ref "U$4") (pin "1") (pinfunction "VDD_1") (pintype "power_in"))
    )
    (net (code "4") (name "/12V-KICKER") (class "Default")
      (node (ref "C18") (pin "1") (pinfunction "1_1") (pintype "passive"))
      (node (ref "C20") (pin "1") (pinfunction "1_1") (pintype "passive"))
      (node (ref "C21") (pin "1") (pinfunction "1_1") (pintype "passive"))
      (node (ref "C23") (pin "1") (pinfunction "1_1") (pintype "passive"))
      (node (ref "C34") (pin "1") (pinfunction "1_1") (pintype "passive"))
      (node (ref "CHARGE_U") (pin "P$1") (pinfunction "VT_P$1") (pintype "bidirectional"))
      (node (ref "CHARGE_U") (pin "P$4") (pinfunction "VCC_P$4") (pintype "bidirectional"))
      (node (ref "KICKER1") (pin "2") (pinfunction "2_2") (pintype "passive"))
      (node (ref "U$3") (pin "P$4") (pinfunction "P$4_P$4") (pintype "bidirectional"))
      (node (ref "U$3") (pin "P$5") (pinfunction "P$5_P$5") (pintype "bidirectional"))
    )
    (net (code "5") (name "/12VGND") (class "Default")
      (node (ref "12VGND") (pin "P$1") (pinfunction "P$1_P$1") (pintype "bidirectional"))
      (node (ref "BATCLAMP2") (pin "A") (pinfunction "A_A") (pintype "passive"))
      (node (ref "BATT") (pin "2") (pinfunction "KL_2") (pintype "passive"))
      (node (ref "C14") (pin "-") (pinfunction "-_-") (pintype "passive"))
      (node (ref "C18") (pin "2") (pinfunction "2_2") (pintype "passive"))
      (node (ref "C19") (pin "2") (pinfunction "2_2") (pintype "passive"))
      (node (ref "C2") (pin "2") (pinfunction "2_2") (pintype "passive"))
      (node (ref "C20") (pin "2") (pinfunction "2_2") (pintype "passive"))
      (node (ref "C21") (pin "2") (pinfunction "2_2") (pintype "passive"))
      (node (ref "C23") (pin "2") (pinfunction "2_2") (pintype "passive"))
      (node (ref "C3") (pin "2") (pinfunction "2_2") (pintype "passive"))
      (node (ref "C34") (pin "2") (pinfunction "2_2") (pintype "passive"))
      (node (ref "C4") (pin "2") (pinfunction "2_2") (pintype "passive"))
      (node (ref "C5") (pin "2") (pinfunction "2_2") (pintype "passive"))
      (node (ref "C6") (pin "-") (pinfunction "-_-") (pintype "passive"))
      (node (ref "C7") (pin "2") (pinfunction "2_2") (pintype "passive"))
      (node (ref "CAP_SENSE_BUF") (pin "2") (pinfunction "V-_2") (pintype "power_in"))
      (node (ref "CHARGE_U") (pin "P$5") (pinfunction "GND_P$5") (pintype "bidirectional"))
      (node (ref "CLAMP2") (pin "A") (pinfunction "A_A") (pintype "passive"))
      (node (ref "DRIB_TRAN") (pin "SOURCE") (pinfunction "S_SOURCE") (pintype "bidirectional"))
      (node (ref "KICK_Q") (pin "SOURCE") (pinfunction "S_SOURCE") (pintype "bidirectional"))
      (node (ref "KICK_Q1") (pin "SOURCE") (pinfunction "S_SOURCE") (pintype "bidirectional"))
      (node (ref "NEON") (pin "2") (pinfunction "2_2") (pintype "passive"))
      (node (ref "R13") (pin "2") (pinfunction "2_2") (pintype "passive"))
      (node (ref "R15") (pin "1") (pinfunction "1_1") (pintype "passive"))
      (node (ref "R18") (pin "1") (pinfunction "1_1") (pintype "passive"))
      (node (ref "R21") (pin "1") (pinfunction "1_1") (pintype "passive"))
      (node (ref "R25") (pin "2") (pinfunction "2_2") (pintype "passive"))
      (node (ref "RBG") (pin "1") (pinfunction "1_1") (pintype "passive"))
      (node (ref "RSENSE") (pin "1") (pinfunction "1_1") (pintype "passive"))
      (node (ref "U$1") (pin "2") (pinfunction "GND_2") (pintype "power_in"))
      (node (ref "U$11") (pin "2") (pinfunction "2_2") (pintype "passive"))
      (node (ref "U$12") (pin "+") (pinfunction "+_+") (pintype "bidirectional"))
      (node (ref "U$13") (pin "2") (pinfunction "2_2") (pintype "passive"))
      (node (ref "U$19") (pin "1") (pinfunction "P$1_1") (pintype "bidirectional"))
      (node (ref "U$3") (pin "P$10") (pinfunction "P$10_P$10") (pintype "bidirectional"))
      (node (ref "U$4") (pin "2") (pinfunction "GND_2") (pintype "power_in"))
      (node (ref "U$5") (pin "3") (pinfunction "S2_3") (pintype "bidirectional"))
      (node (ref "U$6") (pin "LEFT") (pinfunction "COLLECTOR_LEFT") (pintype "bidirectional"))
    )
    (net (code "6") (name "/BAT+") (class "Default")
      (node (ref "BATT") (pin "1") (pinfunction "KL_1") (pintype "passive"))
      (node (ref "ON/OFF") (pin "COM") (pinfunction "COM_COM") (pintype "bidirectional"))
      (node (ref "ON/OFF") (pin "IN1") (pinfunction "P1_IN1") (pintype "bidirectional"))
    )
    (net (code "7") (name "/BATSENSE") (class "Default")
      (node (ref "BAT") (pin "P$1") (pinfunction "P$1_P$1") (pintype "bidirectional"))
      (node (ref "BATCLAMP2") (pin "C") (pinfunction "C_C") (pintype "passive"))
      (node (ref "R17") (pin "1") (pinfunction "1_1") (pintype "passive"))
      (node (ref "R18") (pin "2") (pinfunction "2_2") (pintype "passive"))
      (node (ref "U$14") (pin "23/A9") (pinfunction "23/A9_23/A9") (pintype "bidirectional"))
    )
    (net (code "8") (name "/BB_IN") (class "Default")
      (node (ref "BB_CON") (pin "2") (pinfunction "P$2_2") (pintype "bidirectional"))
      (node (ref "U$14") (pin "31/A12") (pinfunction "31/A12_31/A12") (pintype "bidirectional"))
    )
    (net (code "9") (name "/BB_OUT") (class "Default")
      (node (ref "R19") (pin "1") (pinfunction "1_1") (pintype "passive"))
      (node (ref "U$14") (pin "32/A13") (pinfunction "32/A13_32/A13") (pintype "bidirectional"))
    )
    (net (code "10") (name "/BREN1") (class "Default")
      (node (ref "J3") (pin "6") (pinfunction "6_6") (pintype "passive"))
      (node (ref "U$21") (pin "26") (pinfunction "GPA5_26") (pintype "bidirectional"))
    )
    (net (code "11") (name "/BREN2") (class "Default")
      (node (ref "J4") (pin "6") (pinfunction "6_6") (pintype "passive"))
      (node (ref "U$21") (pin "3") (pinfunction "GPB2_3") (pintype "bidirectional"))
    )
    (net (code "12") (name "/CAP+") (class "Default")
      (node (ref "C14") (pin "+") (pinfunction "+_+") (pintype "passive"))
      (node (ref "C6") (pin "+") (pinfunction "+_+") (pintype "passive"))
      (node (ref "CAP+_TEST") (pin "P$1") (pinfunction "P$1_P$1") (pintype "bidirectional"))
      (node (ref "CHARGE_D") (pin "C") (pinfunction "C_C") (pintype "passive"))
      (node (ref "CHIP") (pin "1") (pinfunction "P$1_1") (pintype "bidirectional"))
      (node (ref "CHIP_FLY") (pin "CATHODE") (pinfunction "C_CATHODE") (pintype "passive"))
      (node (ref "KICK") (pin "1") (pinfunction "P$1_1") (pintype "bidirectional"))
      (node (ref "KICK_FLY") (pin "CATHODE") (pinfunction "C_CATHODE") (pintype "passive"))
      (node (ref "R14") (pin "2") (pinfunction "2_2") (pintype "passive"))
      (node (ref "R24") (pin "2") (pinfunction "2_2") (pintype "passive"))
      (node (ref "U$7") (pin "+") (pinfunction "D+_+") (pintype "bidirectional"))
    )
    (net (code "13") (name "/CHARGE") (class "Default")
      (node (ref "CHARGE") (pin "P$1") (pinfunction "P$1_P$1") (pintype "bidirectional"))
      (node (ref "CHARGE_LED") (pin "A") (pinfunction "A_A") (pintype "passive"))
      (node (ref "CHARGE_U") (pin "P$3") (pinfunction "CHRG_P$3") (pintype "bidirectional"))
      (node (ref "U$14") (pin "0/RX") (pinfunction "0/RX_0/RX") (pintype "bidirectional"))
    )
    (net (code "14") (name "/CHARGE_DONE") (class "Default")
      (node (ref "CHARGE_U") (pin "P$2") (pinfunction "~{DN}_P$2") (pintype "bidirectional"))
      (node (ref "DONE") (pin "P$1") (pinfunction "P$1_P$1") (pintype "bidirectional"))
      (node (ref "R12") (pin "2") (pinfunction "2_2") (pintype "passive"))
      (node (ref "R22") (pin "2") (pinfunction "2_2") (pintype "passive"))
      (node (ref "U$14") (pin "1/TX") (pinfunction "1/TX_1/TX") (pintype "bidirectional"))
    )
    (net (code "15") (name "/CHIP") (class "Default")
      (node (ref "ANDS") (pin "P$3") (pinfunction "Y2_P$3") (pintype "bidirectional"))
      (node (ref "CHIP_LED") (pin "A") (pinfunction "A_A") (pintype "passive"))
      (node (ref "U$1") (pin "3") (pinfunction "IN+_3") (pintype "input"))
    )
    (net (code "16") (name "/CHIP_ENABLE") (class "Default")
      (node (ref "ANDS") (pin "P$6") (pinfunction "B2_P$6") (pintype "bidirectional"))
      (node (ref "CE_LED") (pin "A") (pinfunction "A_A") (pintype "passive"))
      (node (ref "U$14") (pin "5") (pinfunction "5_5") (pintype "bidirectional"))
    )
    (net (code "17") (name "/CS_0") (class "Default")
      (node (ref "C22") (pin "1") (pinfunction "1_1") (pintype "passive"))
      (node (ref "R36") (pin "1") (pinfunction "1_1") (pintype "passive"))
      (node (ref "U$17") (pin "3") (pinfunction "GPB2_3") (pintype "bidirectional"))
    )
    (net (code "18") (name "/CTS") (class "Default")
      (node (ref "R30") (pin "1") (pinfunction "1_1") (pintype "passive"))
      (node (ref "U$14") (pin "24") (pinfunction "24_24") (pintype "bidirectional"))
    )
    (net (code "19") (name "/DIR1") (class "Default")
      (node (ref "J3") (pin "4") (pinfunction "4_4") (pintype "passive"))
      (node (ref "U$21") (pin "27") (pinfunction "GPA6_27") (pintype "bidirectional"))
    )
    (net (code "20") (name "/DIR2") (class "Default")
      (node (ref "J4") (pin "4") (pinfunction "4_4") (pintype "passive"))
      (node (ref "U$21") (pin "2") (pinfunction "GPB1_2") (pintype "bidirectional"))
    )
    (net (code "21") (name "/DISCHARGE") (class "Default")
      (node (ref "R26") (pin "1") (pinfunction "1_1") (pintype "passive"))
      (node (ref "U$14") (pin "4/CANRX") (pinfunction "4/CANRX_4/CANRX") (pintype "bidirectional"))
    )
    (net (code "22") (name "/DIVCAP") (class "Default")
      (node (ref "CAP/100") (pin "P$1") (pinfunction "P$1_P$1") (pintype "bidirectional"))
      (node (ref "CAP_SENSE_BUF") (pin "1") (pinfunction "OUT_1") (pintype "output"))
      (node (ref "CAP_SENSE_BUF") (pin "4") (pinfunction "-IN_4") (pintype "input"))
      (node (ref "R8") (pin "1") (pinfunction "1_1") (pintype "passive"))
    )
    (net (code "23") (name "/DRIB") (class "Default")
      (node (ref "DRIB_TEST") (pin "P$1") (pinfunction "P$1_P$1") (pintype "bidirectional"))
      (node (ref "DRIB_TRAN") (pin "GATE") (pinfunction "G_GATE") (pintype "bidirectional"))
      (node (ref "U$14") (pin "6") (pinfunction "6_6") (pintype "bidirectional"))
    )
    (net (code "24") (name "/ENABLE1") (class "Default")
      (node (ref "J3") (pin "8") (pinfunction "8_8") (pintype "passive"))
      (node (ref "U$21") (pin "25") (pinfunction "GPA4_25") (pintype "bidirectional"))
    )
    (net (code "25") (name "/ENABLE2") (class "Default")
      (node (ref "J4") (pin "8") (pinfunction "8_8") (pintype "passive"))
      (node (ref "U$21") (pin "4") (pinfunction "GPB3_4") (pintype "bidirectional"))
    )
    (net (code "26") (name "/ENA_0") (class "Default")
      (node (ref "R39") (pin "1") (pinfunction "1_1") (pintype "passive"))
      (node (ref "R42") (pin "1") (pinfunction "1_1") (pintype "passive"))
      (node (ref "U$17") (pin "2") (pinfunction "GPB1_2") (pintype "bidirectional"))
    )
    (net (code "27") (name "/ENB_0") (class "Default")
      (node (ref "R40") (pin "1") (pinfunction "1_1") (pintype "passive"))
      (node (ref "R41") (pin "1") (pinfunction "1_1") (pintype "passive"))
      (node (ref "U$17") (pin "4") (pinfunction "GPB3_4") (pintype "bidirectional"))
    )
    (net (code "28") (name "/FAULT1") (class "Default")
      (node (ref "J3") (pin "10") (pinfunction "10_10") (pintype "passive"))
      (node (ref "U$21") (pin "24") (pinfunction "GPA3_24") (pintype "bidirectional"))
    )
    (net (code "29") (name "/FAULT2") (class "Default")
      (node (ref "J4") (pin "10") (pinfunction "10_10") (pintype "passive"))
      (node (ref "U$21") (pin "5") (pinfunction "GPB4_5") (pintype "bidirectional"))
    )
    (net (code "30") (name "/GND") (class "Default")
      (node (ref "3.3REG1") (pin "DRAIN") (pinfunction "GND_DRAIN") (pintype "bidirectional"))
      (node (ref "5REG") (pin "DRAIN") (pinfunction "GND_DRAIN") (pintype "bidirectional"))
      (node (ref "ANDS") (pin "P$4") (pinfunction "GND_P$4") (pintype "bidirectional"))
      (node (ref "BB_CON") (pin "3") (pinfunction "P$3_3") (pintype "bidirectional"))
      (node (ref "BB_CON") (pin "5") (pinfunction "P$5_5") (pintype "bidirectional"))
      (node (ref "C10") (pin "1") (pinfunction "1_1") (pintype "passive"))
      (node (ref "C11") (pin "2") (pinfunction "2_2") (pintype "passive"))
      (node (ref "C12") (pin "2") (pinfunction "2_2") (pintype "passive"))
      (node (ref "C13") (pin "1") (pinfunction "1_1") (pintype "passive"))
      (node (ref "C15") (pin "2") (pinfunction "2_2") (pintype "passive"))
      (node (ref "C16") (pin "2") (pinfunction "2_2") (pintype "passive"))
      (node (ref "C17") (pin "2") (pinfunction "2_2") (pintype "passive"))
      (node (ref "C22") (pin "2") (pinfunction "2_2") (pintype "passive"))
      (node (ref "C24") (pin "2") (pinfunction "2_2") (pintype "passive"))
      (node (ref "C33") (pin "2") (pinfunction "2_2") (pintype "passive"))
      (node (ref "C35") (pin "2") (pinfunction "2_2") (pintype "passive"))
      (node (ref "C36") (pin "2") (pinfunction "2_2") (pintype "passive"))
      (node (ref "C37") (pin "2") (pinfunction "2_2") (pintype "passive"))
      (node (ref "C38") (pin "2") (pinfunction "2_2") (pintype "passive"))
      (node (ref "C39") (pin "2") (pinfunction "2_2") (pintype "passive"))
      (node (ref "C40") (pin "2") (pinfunction "2_2") (pintype "passive"))
      (node (ref "C41") (pin "2") (pinfunction "2_2") (pintype "passive"))
      (node (ref "C8") (pin "2") (pinfunction "2_2") (pintype "passive"))
      (node (ref "C9") (pin "2") (pinfunction "2_2") (pintype "passive"))
      (node (ref "GND") (pin "P$1") (pinfunction "P$1_P$1") (pintype "bidirectional"))
      (node (ref "J3") (pin "1") (pinfunction "1_1") (pintype "passive"))
      (node (ref "J4") (pin "1") (pinfunction "1_1") (pintype "passive"))
      (node (ref "J5") (pin "3") (pinfunction "3_3") (pintype "passive"))
      (node (ref "J6") (pin "3") (pinfunction "3_3") (pintype "passive"))
      (node (ref "J7") (pin "3") (pinfunction "3_3") (pintype "passive"))
      (node (ref "J8") (pin "3") (pinfunction "3_3") (pintype "passive"))
      (node (ref "JP1") (pin "3") (pinfunction "3_3") (pintype "passive"))
      (node (ref "R10") (pin "1") (pinfunction "1_1") (pintype "passive"))
      (node (ref "R11") (pin "2") (pinfunction "2_2") (pintype "passive"))
      (node (ref "R4") (pin "2") (pinfunction "2_2") (pintype "passive"))
      (node (ref "R45") (pin "2") (pinfunction "2_2") (pintype "passive"))
      (node (ref "R47") (pin "2") (pinfunction "2_2") (pintype "passive"))
      (node (ref "R49") (pin "2") (pinfunction "2_2") (pintype "passive"))
      (node (ref "R5") (pin "2") (pinfunction "2_2") (pintype "passive"))
      (node (ref "R51") (pin "2") (pinfunction "2_2") (pintype "passive"))
      (node (ref "R53") (pin "2") (pinfunction "2_2") (pintype "passive"))
      (node (ref "R55") (pin "2") (pinfunction "2_2") (pintype "passive"))
      (node (ref "R57") (pin "2") (pinfunction "2_2") (pintype "passive"))
      (node (ref "R59") (pin "2") (pinfunction "2_2") (pintype "passive"))
      (node (ref "R60") (pin "1") (pinfunction "1_1") (pintype "passive"))
      (node (ref "R61") (pin "1") (pinfunction "1_1") (pintype "passive"))
      (node (ref "R9") (pin "1") (pinfunction "1_1") (pintype "passive"))
      (node (ref "U$14") (pin "AGND") (pinfunction "AGND_AGND") (pintype "bidirectional"))
      (node (ref "U$14") (pin "GND") (pinfunction "GND_GND") (pintype "bidirectional"))
      (node (ref "U$14") (pin "GND2") (pinfunction "GND2_GND2") (pintype "bidirectional"))
      (node (ref "U$15") (pin "10") (pinfunction "GND_10") (pintype "power_in"))
      (node (ref "U$16") (pin "17") (pinfunction "GNDB_17") (pintype "bidirectional"))
      (node (ref "U$16") (pin "18") (pinfunction "GNDB_18") (pintype "bidirectional"))
      (node (ref "U$16") (pin "19") (pinfunction "GNDB_19") (pintype "bidirectional"))
      (node (ref "U$16") (pin "20") (pinfunction "GNDB_20") (pintype "bidirectional"))
      (node (ref "U$16") (pin "26") (pinfunction "GNDA_26") (pintype "bidirectional"))
      (node (ref "U$16") (pin "27") (pinfunction "GNDA_27") (pintype "bidirectional"))
      (node (ref "U$16") (pin "28") (pinfunction "GNDA_28") (pintype "bidirectional"))
      (node (ref "U$16") (pin "29") (pinfunction "GNDA_29") (pintype "bidirectional"))
      (node (ref "U$17") (pin "10") (pinfunction "VSS_10") (pintype "bidirectional"))
      (node (ref "U$17") (pin "15") (pinfunction "A0_15") (pintype "bidirectional"))
      (node (ref "U$17") (pin "16") (pinfunction "A1_16") (pintype "bidirectional"))
      (node (ref "U$17") (pin "17") (pinfunction "A2_17") (pintype "bidirectional"))
      (node (ref "U$18") (pin "1") (pinfunction "EOUT_1") (pintype "bidirectional"))
      (node (ref "U$18") (pin "4") (pinfunction "VCC_4") (pintype "bidirectional"))
      (node (ref "U$19") (pin "2") (pinfunction "P$2_2") (pintype "bidirectional"))
      (node (ref "U$21") (pin "10") (pinfunction "VSS_10") (pintype "bidirectional"))
      (node (ref "U$21") (pin "15") (pinfunction "A0_15") (pintype "bidirectional"))
      (node (ref "U$21") (pin "16") (pinfunction "A1_16") (pintype "bidirectional"))
      (node (ref "U$22") (pin "S") (pinfunction "S_S") (pintype "bidirectional"))
      (node (ref "U$5") (pin "2") (pinfunction "LED-_2") (pintype "bidirectional"))
      (node (ref "U$8") (pin "1") (pinfunction "GND_1") (pintype "bidirectional"))
    )
    (net (code "31") (name "/HALLOUT1") (class "Default")
      (node (ref "J3") (pin "9") (pinfunction "9_9") (pintype "passive"))
    )
    (net (code "32") (name "/HALLOUT2") (class "Default")
      (node (ref "J4") (pin "9") (pinfunction "9_9") (pintype "passive"))
    )
    (net (code "33") (name "/INA_0") (class "Default")
      (node (ref "R63") (pin "2") (pinfunction "2_2") (pintype "passive"))
      (node (ref "U$17") (pin "1") (pinfunction "GPB0_1") (pintype "bidirectional"))
    )
    (net (code "34") (name "/INB_0") (class "Default")
      (node (ref "R62") (pin "2") (pinfunction "2_2") (pintype "passive"))
      (node (ref "U$17") (pin "5") (pinfunction "GPB4_5") (pintype "bidirectional"))
    )
    (net (code "35") (name "/INT1") (class "Default")
      (node (ref "U$14") (pin "9/CS") (pinfunction "9/CS_9/CS") (pintype "bidirectional"))
      (node (ref "U$17") (pin "20") (pinfunction "INTA_20") (pintype "bidirectional"))
    )
    (net (code "36") (name "/INT2") (class "Default")
      (node (ref "U$14") (pin "39/A20") (pinfunction "39/A20_39/A20") (pintype "bidirectional"))
      (node (ref "U$21") (pin "20") (pinfunction "INTA_20") (pintype "bidirectional"))
    )
    (net (code "37") (name "/KICK") (class "Default")
      (node (ref "ANDS") (pin "P$7") (pinfunction "Y1_P$7") (pintype "bidirectional"))
      (node (ref "KICK_LED") (pin "A") (pinfunction "A_A") (pintype "passive"))
      (node (ref "U$4") (pin "3") (pinfunction "IN+_3") (pintype "input"))
    )
    (net (code "38") (name "/KICK_ENABLE") (class "Default")
      (node (ref "ANDS") (pin "P$2") (pinfunction "B1_P$2") (pintype "bidirectional"))
      (node (ref "KE_LED") (pin "A") (pinfunction "A_A") (pintype "passive"))
      (node (ref "U$14") (pin "7") (pinfunction "7_7") (pintype "bidirectional"))
    )
    (net (code "39") (name "/KICK_REF") (class "Default")
      (node (ref "R37") (pin "1") (pinfunction "1_1") (pintype "passive"))
      (node (ref "U$14") (pin "A22/DAC1") (pinfunction "A22/DAC1_A22/DAC1") (pintype "bidirectional"))
    )
    (net (code "40") (name "/LOCKN1") (class "Default")
      (node (ref "J3") (pin "2") (pinfunction "2_2") (pintype "passive"))
      (node (ref "U$21") (pin "28") (pinfunction "GPA7_28") (pintype "bidirectional"))
    )
    (net (code "41") (name "/LOCKN2") (class "Default")
      (node (ref "J4") (pin "2") (pinfunction "2_2") (pintype "passive"))
      (node (ref "U$21") (pin "1") (pinfunction "GPB0_1") (pintype "bidirectional"))
    )
    (net (code "42") (name "/M1QA-1") (class "Default")
      (node (ref "J5") (pin "2") (pinfunction "2_2") (pintype "passive"))
      (node (ref "R58") (pin "2") (pinfunction "2_2") (pintype "passive"))
    )
    (net (code "43") (name "/M1QA-1OUT") (class "Default")
      (node (ref "R58") (pin "1") (pinfunction "1_1") (pintype "passive"))
      (node (ref "R59") (pin "1") (pinfunction "1_1") (pintype "passive"))
      (node (ref "U$14") (pin "27") (pinfunction "27_27") (pintype "bidirectional"))
    )
    (net (code "44") (name "/M1QA-2") (class "Default")
      (node (ref "J6") (pin "2") (pinfunction "2_2") (pintype "passive"))
      (node (ref "R52") (pin "2") (pinfunction "2_2") (pintype "passive"))
    )
    (net (code "45") (name "/M1QA-2OUT") (class "Default")
      (node (ref "R52") (pin "1") (pinfunction "1_1") (pintype "passive"))
      (node (ref "R53") (pin "1") (pinfunction "1_1") (pintype "passive"))
      (node (ref "U$14") (pin "17/A3") (pinfunction "17/A3_17/A3") (pintype "bidirectional"))
    )
    (net (code "46") (name "/M1QA-3") (class "Default")
      (node (ref "J7") (pin "2") (pinfunction "2_2") (pintype "passive"))
      (node (ref "R54") (pin "2") (pinfunction "2_2") (pintype "passive"))
    )
    (net (code "47") (name "/M1QA-3OUT") (class "Default")
      (node (ref "R54") (pin "1") (pinfunction "1_1") (pintype "passive"))
      (node (ref "R55") (pin "1") (pinfunction "1_1") (pintype "passive"))
      (node (ref "U$14") (pin "15/A1") (pinfunction "15/A1_15/A1") (pintype "bidirectional"))
    )
    (net (code "48") (name "/M1QA-4") (class "Default")
      (node (ref "J8") (pin "2") (pinfunction "2_2") (pintype "passive"))
      (node (ref "R56") (pin "2") (pinfunction "2_2") (pintype "passive"))
    )
    (net (code "49") (name "/M1QA-4OUT") (class "Default")
      (node (ref "R56") (pin "1") (pinfunction "1_1") (pintype "passive"))
      (node (ref "R57") (pin "1") (pinfunction "1_1") (pintype "passive"))
      (node (ref "U$14") (pin "25") (pinfunction "25_25") (pintype "bidirectional"))
    )
    (net (code "50") (name "/M1QB-1") (class "Default")
      (node (ref "J5") (pin "4") (pinfunction "4_4") (pintype "passive"))
      (node (ref "R50") (pin "2") (pinfunction "2_2") (pintype "passive"))
    )
    (net (code "51") (name "/M1QB-1OUT") (class "Default")
      (node (ref "R50") (pin "1") (pinfunction "1_1") (pintype "passive"))
      (node (ref "R51") (pin "1") (pinfunction "1_1") (pintype "passive"))
      (node (ref "U$14") (pin "28") (pinfunction "28_28") (pintype "bidirectional"))
    )
    (net (code "52") (name "/M1QB-2") (class "Default")
      (node (ref "J6") (pin "4") (pinfunction "4_4") (pintype "passive"))
      (node (ref "R44") (pin "2") (pinfunction "2_2") (pintype "passive"))
    )
    (net (code "53") (name "/M1QB-2OUT") (class "Default")
      (node (ref "R44") (pin "1") (pinfunction "1_1") (pintype "passive"))
      (node (ref "R45") (pin "1") (pinfunction "1_1") (pintype "passive"))
      (node (ref "U$14") (pin "16/A2") (pinfunction "16/A2_16/A2") (pintype "bidirectional"))
    )
    (net (code "54") (name "/M1QB-3") (class "Default")
      (node (ref "J7") (pin "4") (pinfunction "4_4") (pintype "passive"))
      (node (ref "R46") (pin "2") (pinfunction "2_2") (pintype "passive"))
    )
    (net (code "55") (name "/M1QB-3OUT") (class "Default")
      (node (ref "R46") (pin "1") (pinfunction "1_1") (pintype "passive"))
      (node (ref "R47") (pin "1") (pinfunction "1_1") (pintype "passive"))
      (node (ref "U$14") (pin "14/A0") (pinfunction "14/A0_14/A0") (pintype "bidirectional"))
    )
    (net (code "56") (name "/M1QB-4") (class "Default")
      (node (ref "J8") (pin "4") (pinfunction "4_4") (pintype "passive"))
      (node (ref "R48") (pin "2") (pinfunction "2_2") (pintype "passive"))
    )
    (net (code "57") (name "/M1QB-4OUT") (class "Default")
      (node (ref "R48") (pin "1") (pinfunction "1_1") (pintype "passive"))
      (node (ref "R49") (pin "1") (pinfunction "1_1") (pintype "passive"))
      (node (ref "U$14") (pin "26") (pinfunction "26_26") (pintype "bidirectional"))
    )
    (net (code "58") (name "/N$38") (class "Default")
      (node (ref "C13") (pin "2") (pinfunction "2_2") (pintype "passive"))
      (node (ref "R32") (pin "1") (pinfunction "1_1") (pintype "passive"))
      (node (ref "U$8") (pin "7") (pinfunction "VREF2_7") (pintype "bidirectional"))
      (node (ref "U$8") (pin "8") (pinfunction "EN_8") (pintype "bidirectional"))
    )
    (net (code "59") (name "/OUTA") (class "Default")
      (node (ref "GREEN_DIR") (pin "C") (pinfunction "C_C") (pintype "passive"))
      (node (ref "JP1") (pin "1") (pinfunction "1_1") (pintype "passive"))
      (node (ref "RED_DIR") (pin "A") (pinfunction "A_A") (pintype "passive"))
      (node (ref "U$16") (pin "1") (pinfunction "OUTA_1") (pintype "bidirectional"))
      (node (ref "U$16") (pin "24") (pinfunction "OUTA_24") (pintype "bidirectional"))
      (node (ref "U$16") (pin "25") (pinfunction "OUTA_25") (pintype "bidirectional"))
      (node (ref "U$16") (pin "30") (pinfunction "OUTA_30") (pintype "bidirectional"))
      (node (ref "U$16") (pin "OUTA") (pinfunction "OUTA_OUTA") (pintype "bidirectional"))
      (node (ref "U$16") (pin "OUTA@1") (pinfunction "OUTA_OUTA@1") (pintype "bidirectional"))
    )
    (net (code "60") (name "/OUTB") (class "Default")
      (node (ref "JP1") (pin "2") (pinfunction "2_2") (pintype "passive"))
      (node (ref "R38") (pin "1") (pinfunction "1_1") (pintype "passive"))
      (node (ref "U$16") (pin "15") (pinfunction "OUTB_15") (pintype "bidirectional"))
      (node (ref "U$16") (pin "16") (pinfunction "OUTB_16") (pintype "bidirectional"))
      (node (ref "U$16") (pin "21") (pinfunction "OUTB_21") (pintype "bidirectional"))
      (node (ref "U$16") (pin "22") (pinfunction "OUTB_22") (pintype "bidirectional"))
      (node (ref "U$16") (pin "OUTB") (pinfunction "OUTB_OUTB") (pintype "bidirectional"))
      (node (ref "U$16") (pin "OUTB@1") (pinfunction "OUTB_OUTB@1") (pintype "bidirectional"))
    )
    (net (code "61") (name "/PWM0") (class "Default")
      (node (ref "R35") (pin "1") (pinfunction "1_1") (pintype "passive"))
      (node (ref "R60") (pin "2") (pinfunction "2_2") (pintype "passive"))
      (node (ref "U$14") (pin "10/CS") (pinfunction "10/CS_10/CS") (pintype "bidirectional"))
    )
    (net (code "62") (name "/PWM1") (class "Default")
      (node (ref "J3") (pin "7") (pinfunction "7_7") (pintype "passive"))
      (node (ref "U$14") (pin "2") (pinfunction "2_2") (pintype "bidirectional"))
    )
    (net (code "63") (name "/PWM2") (class "Default")
      (node (ref "J4") (pin "7") (pinfunction "7_7") (pintype "passive"))
      (node (ref "U$14") (pin "3/CANTX") (pinfunction "3/CANTX_3/CANTX") (pintype "bidirectional"))
    )
    (net (code "64") (name "/PWM3") (class "Default")
      (node (ref "U$14") (pin "29") (pinfunction "29_29") (pintype "bidirectional"))
    )
    (net (code "65") (name "/RTS") (class "Default")
      (node (ref "R28") (pin "1") (pinfunction "1_1") (pintype "passive"))
      (node (ref "U$14") (pin "35/A16") (pinfunction "35/A16_35/A16") (pintype "bidirectional"))
    )
    (net (code "66") (name "/RX") (class "Default")
      (node (ref "U$14") (pin "34/A15") (pinfunction "34/A15_34/A15") (pintype "bidirectional"))
      (node (ref "U$15") (pin "2") (pinfunction "DOUT_2") (pintype "output"))
    )
    (net (code "67") (name "/SCL") (class "Default")
      (node (ref "R27") (pin "1") (pinfunction "1_1") (pintype "passive"))
      (node (ref "U$14") (pin "19/A5/SCL") (pinfunction "19/A5/SCL_19/A5/SCL") (pintype "bidirectional"))
      (node (ref "U$8") (pin "3") (pinfunction "SCL1_3") (pintype "bidirectional"))
    )
    (net (code "68") (name "/SCL-H") (class "Default")
      (node (ref "R33") (pin "1") (pinfunction "1_1") (pintype "passive"))
      (node (ref "U$17") (pin "12") (pinfunction "SCK_12") (pintype "bidirectional"))
      (node (ref "U$21") (pin "12") (pinfunction "SCK_12") (pintype "bidirectional"))
      (node (ref "U$8") (pin "6") (pinfunction "SCL2_6") (pintype "bidirectional"))
    )
    (net (code "69") (name "/SDA") (class "Default")
      (node (ref "R7") (pin "1") (pinfunction "1_1") (pintype "passive"))
      (node (ref "U$14") (pin "18/A4/SDA") (pinfunction "18/A4/SDA_18/A4/SDA") (pintype "bidirectional"))
      (node (ref "U$8") (pin "4") (pinfunction "SDA1_4") (pintype "bidirectional"))
    )
    (net (code "70") (name "/SDA-H") (class "Default")
      (node (ref "R34") (pin "1") (pinfunction "1_1") (pintype "passive"))
      (node (ref "U$17") (pin "13") (pinfunction "SDA_13") (pintype "bidirectional"))
      (node (ref "U$21") (pin "13") (pinfunction "SDA_13") (pintype "bidirectional"))
      (node (ref "U$8") (pin "5") (pinfunction "SDA2_5") (pintype "bidirectional"))
    )
    (net (code "71") (name "/TX") (class "Default")
      (node (ref "U$14") (pin "33/A14") (pinfunction "33/A14_33/A14") (pintype "bidirectional"))
      (node (ref "U$15") (pin "3") (pinfunction "DIN_3") (pintype "input"))
    )
    (net (code "72") (name "/XBRST") (class "Default")
      (node (ref "U$15") (pin "5") (pinfunction "RESET_5") (pintype "input"))
    )
    (net (code "73") (name "Net-(ANDS-A1)") (class "Default")
      (node (ref "ANDS") (pin "P$1") (pinfunction "A1_P$1") (pintype "bidirectional"))
      (node (ref "ANDS") (pin "P$5") (pinfunction "A2_P$5") (pintype "bidirectional"))
      (node (ref "R29") (pin "2") (pinfunction "2_2") (pintype "passive"))
      (node (ref "U$18") (pin "7") (pinfunction "COUT_7") (pintype "bidirectional"))
      (node (ref "U$22") (pin "G") (pinfunction "G_G") (pintype "bidirectional"))
    )
    (net (code "74") (name "Net-(BB_CON-P$1)") (class "Default")
      (node (ref "BB_CON") (pin "1") (pinfunction "P$1_1") (pintype "bidirectional"))
      (node (ref "R20") (pin "2") (pinfunction "2_2") (pintype "passive"))
    )
    (net (code "75") (name "Net-(BB_CON-P$4)") (class "Default")
      (node (ref "BB_CON") (pin "4") (pinfunction "P$4_4") (pintype "bidirectional"))
      (node (ref "R19") (pin "2") (pinfunction "2_2") (pintype "passive"))
    )
    (net (code "76") (name "Net-(CAP_SENSE_BUF-+IN)") (class "Default")
      (node (ref "CAP_SENSE_BUF") (pin "3") (pinfunction "+IN_3") (pintype "input"))
      (node (ref "CLAMP1") (pin "A") (pinfunction "A_A") (pintype "passive"))
      (node (ref "CLAMP2") (pin "C") (pinfunction "C_C") (pintype "passive"))
      (node (ref "R14") (pin "1") (pinfunction "1_1") (pintype "passive"))
      (node (ref "R15") (pin "2") (pinfunction "2_2") (pintype "passive"))
    )
    (net (code "77") (name "Net-(CE_LED-PadC)") (class "Default")
      (node (ref "CE_LED") (pin "C") (pinfunction "C_C") (pintype "passive"))
      (node (ref "R5") (pin "1") (pinfunction "1_1") (pintype "passive"))
    )
    (net (code "78") (name "Net-(CHARGE_D-PadA)") (class "Default")
      (node (ref "CHARGE_D") (pin "A") (pinfunction "A_A") (pintype "passive"))
      (node (ref "U$3") (pin "P$1") (pinfunction "P$1_P$1") (pintype "bidirectional"))
    )
    (net (code "79") (name "Net-(CHARGE_LED-PadC)") (class "Default")
      (node (ref "CHARGE_LED") (pin "C") (pinfunction "C_C") (pintype "passive"))
      (node (ref "R11") (pin "1") (pinfunction "1_1") (pintype "passive"))
    )
    (net (code "80") (name "Net-(CHARGE_U-GATE)") (class "Default")
      (node (ref "CHARGE_U") (pin "P$7") (pinfunction "GATE_P$7") (pintype "bidirectional"))
      (node (ref "R43") (pin "1") (pinfunction "1_1") (pintype "passive"))
    )
    (net (code "81") (name "Net-(CHARGE_U-RBG)") (class "Default")
      (node (ref "C19") (pin "1") (pinfunction "1_1") (pintype "passive"))
      (node (ref "CHARGE_U") (pin "P$10") (pinfunction "RBG_P$10") (pintype "bidirectional"))
      (node (ref "RBG") (pin "2") (pinfunction "2_2") (pintype "passive"))
    )
    (net (code "82") (name "Net-(CHARGE_U-RDCM)") (class "Default")
      (node (ref "CHARGE_U") (pin "P$8") (pinfunction "RDCM_P$8") (pintype "bidirectional"))
      (node (ref "R31") (pin "1") (pinfunction "1_1") (pintype "passive"))
    )
    (net (code "83") (name "Net-(CHARGE_U-RV)") (class "Default")
      (node (ref "CHARGE_U") (pin "P$9") (pinfunction "RV_P$9") (pintype "bidirectional"))
      (node (ref "RVOUT") (pin "1") (pinfunction "1_1") (pintype "passive"))
    )
    (net (code "84") (name "Net-(CHARGE_U-SRC)") (class "Default")
      (node (ref "CHARGE_U") (pin "P$6") (pinfunction "SRC_P$6") (pintype "bidirectional"))
      (node (ref "RSENSE") (pin "2") (pinfunction "2_2") (pintype "passive"))
      (node (ref "SWITCH_Q") (pin "SOURCE") (pinfunction "S_SOURCE") (pintype "bidirectional"))
    )
    (net (code "85") (name "Net-(CHIP-P$2)") (class "Default")
      (node (ref "CHIP") (pin "2") (pinfunction "P$2_2") (pintype "bidirectional"))
      (node (ref "CHIP_FLY") (pin "ANODE") (pinfunction "A_ANODE") (pintype "passive"))
      (node (ref "KICK_Q1") (pin "DRAIN") (pinfunction "D_DRAIN") (pintype "bidirectional"))
    )
    (net (code "86") (name "Net-(CHIP_LED-PadC)") (class "Default")
      (node (ref "CHIP_LED") (pin "C") (pinfunction "C_C") (pintype "passive"))
      (node (ref "R10") (pin "2") (pinfunction "2_2") (pintype "passive"))
    )
    (net (code "87") (name "Net-(DONE_LED-PadC)") (class "Default")
      (node (ref "DONE_LED") (pin "C") (pinfunction "C_C") (pintype "passive"))
      (node (ref "R12") (pin "1") (pinfunction "1_1") (pintype "passive"))
    )
    (net (code "88") (name "Net-(DRIB-P$2)") (class "Default")
      (node (ref "DRIB") (pin "2") (pinfunction "P$2_2") (pintype "bidirectional"))
      (node (ref "DRIB_TRAN") (pin "DRAIN") (pinfunction "D_DRAIN") (pintype "bidirectional"))
    )
    (net (code "89") (name "Net-(GREEN_DIR-PadA)") (class "Default")
      (node (ref "GREEN_DIR") (pin "A") (pinfunction "A_A") (pintype "passive"))
      (node (ref "R38") (pin "2") (pinfunction "2_2") (pintype "passive"))
      (node (ref "RED_DIR") (pin "C") (pinfunction "C_C") (pintype "passive"))
    )
    (net (code "90") (name "Net-(KE_LED-PadC)") (class "Default")
      (node (ref "KE_LED") (pin "C") (pinfunction "C_C") (pintype "passive"))
      (node (ref "R4") (pin "1") (pinfunction "1_1") (pintype "passive"))
    )
    (net (code "91") (name "Net-(KICK-P$2)") (class "Default")
      (node (ref "KICK") (pin "2") (pinfunction "P$2_2") (pintype "bidirectional"))
      (node (ref "KICK_FLY") (pin "ANODE") (pinfunction "A_ANODE") (pintype "passive"))
      (node (ref "KICK_Q") (pin "DRAIN") (pinfunction "D_DRAIN") (pintype "bidirectional"))
    )
    (net (code "92") (name "Net-(KICK_LED-PadC)") (class "Default")
      (node (ref "KICK_LED") (pin "C") (pinfunction "C_C") (pintype "passive"))
      (node (ref "R9") (pin "2") (pinfunction "2_2") (pintype "passive"))
    )
    (net (code "93") (name "Net-(KICK_Q-G)") (class "Default")
      (node (ref "KICK_Q") (pin "GATE") (pinfunction "G_GATE") (pintype "bidirectional"))
      (node (ref "R1") (pin "2") (pinfunction "2_2") (pintype "passive"))
    )
    (net (code "94") (name "Net-(KICK_Q1-G)") (class "Default")
      (node (ref "KICK_Q1") (pin "GATE") (pinfunction "G_GATE") (pintype "bidirectional"))
      (node (ref "R2") (pin "2") (pinfunction "2_2") (pintype "passive"))
    )
    (net (code "95") (name "Net-(KICK_READY-PadC)") (class "Default")
      (node (ref "KICK_READY") (pin "C") (pinfunction "C_C") (pintype "passive"))
      (node (ref "R6") (pin "2") (pinfunction "2_2") (pintype "passive"))
    )
    (net (code "96") (name "Net-(NEON-Pad1)") (class "Default")
      (node (ref "NEON") (pin "1") (pinfunction "1_1") (pintype "passive"))
      (node (ref "R24") (pin "1") (pinfunction "1_1") (pintype "passive"))
    )
    (net (code "97") (name "Net-(PW_LED1-PadC)") (class "Default")
      (node (ref "PW_LED1") (pin "C") (pinfunction "C_C") (pintype "passive"))
      (node (ref "R21") (pin "2") (pinfunction "2_2") (pintype "passive"))
    )
    (net (code "98") (name "Net-(R6-Pad1)") (class "Default")
      (node (ref "R6") (pin "1") (pinfunction "1_1") (pintype "passive"))
      (node (ref "U$22") (pin "D") (pinfunction "D_D") (pintype "bidirectional"))
    )
    (net (code "99") (name "Net-(SWITCH_Q-D)") (class "Default")
      (node (ref "DRAIN") (pin "P$1") (pinfunction "P$1_P$1") (pintype "bidirectional"))
      (node (ref "R31") (pin "2") (pinfunction "2_2") (pintype "passive"))
      (node (ref "RVOUT") (pin "2") (pinfunction "2_2") (pintype "passive"))
      (node (ref "SWITCH_Q") (pin "DRAIN") (pinfunction "D_DRAIN") (pintype "bidirectional"))
      (node (ref "U$3") (pin "P$6") (pinfunction "P$6_P$6") (pintype "bidirectional"))
      (node (ref "U$3") (pin "P$7") (pinfunction "P$7_P$7") (pintype "bidirectional"))
    )
    (net (code "100") (name "Net-(SWITCH_Q-G)") (class "Default")
      (node (ref "GATE") (pin "P$1") (pinfunction "P$1_P$1") (pintype "bidirectional"))
      (node (ref "R43") (pin "2") (pinfunction "2_2") (pintype "passive"))
      (node (ref "SWITCH_Q") (pin "GATE") (pinfunction "G_GATE") (pintype "bidirectional"))
    )
    (net (code "101") (name "Net-(U$1-OUT)") (class "Default")
      (node (ref "R2") (pin "1") (pinfunction "1_1") (pintype "passive"))
      (node (ref "U$1") (pin "5") (pinfunction "OUT_5") (pintype "output"))
    )
    (net (code "102") (name "Net-(U$2-DRAIN)") (class "Default")
      (node (ref "U$2") (pin "TAB") (pinfunction "DRAIN_TAB") (pintype "bidirectional"))
      (node (ref "U$7") (pin "-") (pinfunction "D-_-") (pintype "bidirectional"))
    )
    (net (code "103") (name "Net-(U$2-GATE)") (class "Default")
      (node (ref "R25") (pin "1") (pinfunction "1_1") (pintype "passive"))
      (node (ref "U$2") (pin "LOWER_LEFT") (pinfunction "GATE_LOWER_LEFT") (pintype "bidirectional"))
    )
    (net (code "104") (name "Net-(U$2-SOURCE)") (class "Default")
      (node (ref "R3") (pin "1") (pinfunction "1_1") (pintype "passive"))
      (node (ref "U$2") (pin "LOWER_RIGHT") (pinfunction "SOURCE_LOWER_RIGHT") (pintype "bidirectional"))
      (node (ref "U$6") (pin "RIGHT") (pinfunction "EMITTER_RIGHT") (pintype "bidirectional"))
    )
    (net (code "105") (name "Net-(U$4-OUT)") (class "Default")
      (node (ref "R1") (pin "1") (pinfunction "1_1") (pintype "passive"))
      (node (ref "U$4") (pin "5") (pinfunction "OUT_5") (pintype "output"))
    )
    (net (code "106") (name "Net-(U$5-LED+)") (class "Default")
      (node (ref "R26") (pin "2") (pinfunction "2_2") (pintype "passive"))
      (node (ref "U$5") (pin "1") (pinfunction "LED+_1") (pintype "bidirectional"))
    )
    (net (code "107") (name "Net-(U$5-S1)") (class "Default")
      (node (ref "R16") (pin "1") (pinfunction "1_1") (pintype "passive"))
      (node (ref "R23") (pin "2") (pinfunction "2_2") (pintype "passive"))
      (node (ref "U$5") (pin "4") (pinfunction "S1_4") (pintype "bidirectional"))
    )
    (net (code "108") (name "Net-(U$6-BASE)") (class "Default")
      (node (ref "R13") (pin "1") (pinfunction "1_1") (pintype "passive"))
      (node (ref "R16") (pin "2") (pinfunction "2_2") (pintype "passive"))
      (node (ref "R3") (pin "2") (pinfunction "2_2") (pintype "passive"))
      (node (ref "U$6") (pin "CENTER") (pinfunction "BASE_CENTER") (pintype "bidirectional"))
    )
    (net (code "109") (name "Net-(U$15-CTS)") (class "Default")
      (node (ref "R30") (pin "2") (pinfunction "2_2") (pintype "passive"))
      (node (ref "U$15") (pin "12") (pinfunction "CTS_12") (pintype "output"))
    )
    (net (code "110") (name "Net-(U$15-RTS)") (class "Default")
      (node (ref "R28") (pin "2") (pinfunction "2_2") (pintype "passive"))
      (node (ref "U$15") (pin "16") (pinfunction "RTS_16") (pintype "input"))
    )
    (net (code "111") (name "Net-(U$16-CP)") (class "Default")
      (node (ref "U$16") (pin "11") (pinfunction "CP_11") (pintype "bidirectional"))
      (node (ref "U$20") (pin "1") (pinfunction "G_1") (pintype "bidirectional"))
    )
    (net (code "112") (name "Net-(U$16-CS)") (class "Default")
      (node (ref "R36") (pin "2") (pinfunction "2_2") (pintype "passive"))
      (node (ref "R61") (pin "2") (pinfunction "2_2") (pintype "passive"))
      (node (ref "U$16") (pin "8") (pinfunction "CS_8") (pintype "bidirectional"))
    )
    (net (code "113") (name "Net-(U$16-ENA{slash}DIAGA)") (class "Default")
      (node (ref "R39") (pin "2") (pinfunction "2_2") (pintype "passive"))
      (node (ref "U$16") (pin "5") (pinfunction "ENA/DIAGA_5") (pintype "bidirectional"))
    )
    (net (code "114") (name "Net-(U$16-ENB{slash}DIAGB)") (class "Default")
      (node (ref "R40") (pin "2") (pinfunction "2_2") (pintype "passive"))
      (node (ref "U$16") (pin "9") (pinfunction "ENB/DIAGB_9") (pintype "bidirectional"))
    )
    (net (code "115") (name "Net-(U$16-INA)") (class "Default")
      (node (ref "R63") (pin "1") (pinfunction "1_1") (pintype "passive"))
      (node (ref "U$16") (pin "4") (pinfunction "INA_4") (pintype "bidirectional"))
    )
    (net (code "116") (name "Net-(U$16-INB)") (class "Default")
      (node (ref "R62") (pin "1") (pinfunction "1_1") (pintype "passive"))
      (node (ref "U$16") (pin "10") (pinfunction "INB_10") (pintype "bidirectional"))
    )
    (net (code "117") (name "Net-(U$16-PWM)") (class "Default")
      (node (ref "R35") (pin "2") (pinfunction "2_2") (pintype "passive"))
      (node (ref "U$16") (pin "7") (pinfunction "PWM_7") (pintype "bidirectional"))
    )
    (net (code "118") (name "Net-(U$18-IN+)") (class "Default")
      (node (ref "R8") (pin "2") (pinfunction "2_2") (pintype "passive"))
      (node (ref "U$18") (pin "2") (pinfunction "IN+_2") (pintype "bidirectional"))
    )
    (net (code "119") (name "Net-(U$18-IN-)") (class "Default")
      (node (ref "R37") (pin "2") (pinfunction "2_2") (pintype "passive"))
      (node (ref "U$18") (pin "3") (pinfunction "IN-_3") (pintype "bidirectional"))
    )
    (net (code "120") (name "Net-(U$20-S)") (class "Default")
      (node (ref "C17") (pin "1") (pinfunction "1_1") (pintype "passive"))
      (node (ref "C24") (pin "1") (pinfunction "1_1") (pintype "passive"))
      (node (ref "U$16") (pin "13") (pinfunction "VCC_13") (pintype "bidirectional"))
      (node (ref "U$16") (pin "14") (pinfunction "VCC_14") (pintype "bidirectional"))
      (node (ref "U$16") (pin "2") (pinfunction "VCC_2") (pintype "bidirectional"))
      (node (ref "U$16") (pin "23") (pinfunction "VCC_23") (pintype "bidirectional"))
      (node (ref "U$16") (pin "3") (pinfunction "VCC_3") (pintype "bidirectional"))
      (node (ref "U$16") (pin "VCC") (pinfunction "VCC_VCC") (pintype "bidirectional"))
      (node (ref "U$16") (pin "VCC@1") (pinfunction "VCC_VCC@1") (pintype "bidirectional"))
      (node (ref "U$20") (pin "3") (pinfunction "S_3") (pintype "bidirectional"))
    )
    (net (code "121") (name "unconnected-(C1-Pad1)") (class "Default")
      (node (ref "C1") (pin "1") (pinfunction "1_1") (pintype "passive"))
    )
    (net (code "122") (name "unconnected-(J3-Pad3)") (class "Default")
      (node (ref "J3") (pin "3") (pinfunction "3_3") (pintype "passive"))
    )
    (net (code "123") (name "unconnected-(J3-Pad5)") (class "Default")
      (node (ref "J3") (pin "5") (pinfunction "5_5") (pintype "passive"))
    )
    (net (code "124") (name "unconnected-(J4-Pad3)") (class "Default")
      (node (ref "J4") (pin "3") (pinfunction "3_3") (pintype "passive"))
    )
    (net (code "125") (name "unconnected-(J4-Pad5)") (class "Default")
      (node (ref "J4") (pin "5") (pinfunction "5_5") (pintype "passive"))
    )
    (net (code "126") (name "unconnected-(JP1-Pad5)") (class "Default")
      (node (ref "JP1") (pin "5") (pinfunction "5_5") (pintype "passive"))
    )
    (net (code "127") (name "unconnected-(JP1-Pad6)") (class "Default")
      (node (ref "JP1") (pin "6") (pinfunction "6_6") (pintype "passive"))
    )
    (net (code "128") (name "unconnected-(U$14-A21{slash}DAC0-Pad21{slash}DAC0)") (class "Default")
      (node (ref "U$14") (pin "21/DAC0") (pinfunction "A21/DAC0_21/DAC0") (pintype "bidirectional"))
    )
    (net (code "129") (name "unconnected-(U$14-Pad3V3)") (class "Default")
      (node (ref "U$14") (pin "3V3") (pinfunction "3V3_3V3") (pintype "bidirectional"))
    )
    (net (code "130") (name "unconnected-(U$14-Pad3V3_2)") (class "Default")
      (node (ref "U$14") (pin "3V3_2") (pinfunction "3V3_2_3V3_2") (pintype "bidirectional"))
    )
    (net (code "131") (name "unconnected-(U$14-Pad3V3_LO)") (class "Default")
      (node (ref "U$14") (pin "3V3_LO") (pinfunction "3V3_LO_3V3_LO") (pintype "bidirectional"))
    )
    (net (code "132") (name "unconnected-(U$14-Pad8)") (class "Default")
      (node (ref "U$14") (pin "8") (pinfunction "8_8") (pintype "bidirectional"))
    )
    (net (code "133") (name "unconnected-(U$14-Pad11{slash}MOSI)") (class "Default")
      (node (ref "U$14") (pin "11/MOSI") (pinfunction "11/MOSI_11/MOSI") (pintype "bidirectional"))
    )
    (net (code "134") (name "unconnected-(U$14-Pad12{slash}MISO)") (class "Default")
      (node (ref "U$14") (pin "12/MISO") (pinfunction "12/MISO_12/MISO") (pintype "bidirectional"))
    )
    (net (code "135") (name "unconnected-(U$14-Pad13{slash}SCK)") (class "Default")
      (node (ref "U$14") (pin "13/SCK") (pinfunction "13/SCK_13/SCK") (pintype "bidirectional"))
    )
    (net (code "136") (name "unconnected-(U$14-Pad20{slash}A6)") (class "Default")
      (node (ref "U$14") (pin "20/A6") (pinfunction "20/A6_20/A6") (pintype "bidirectional"))
    )
    (net (code "137") (name "unconnected-(U$14-Pad21{slash}A7)") (class "Default")
      (node (ref "U$14") (pin "21/A7") (pinfunction "21/A7_21/A7") (pintype "bidirectional"))
    )
    (net (code "138") (name "unconnected-(U$14-Pad22{slash}A8)") (class "Default")
      (node (ref "U$14") (pin "22/A8") (pinfunction "22/A8_22/A8") (pintype "bidirectional"))
    )
    (net (code "139") (name "unconnected-(U$14-Pad30)") (class "Default")
      (node (ref "U$14") (pin "30") (pinfunction "30_30") (pintype "bidirectional"))
    )
    (net (code "140") (name "unconnected-(U$14-Pad36{slash}A17)") (class "Default")
      (node (ref "U$14") (pin "36/A17") (pinfunction "36/A17_36/A17") (pintype "bidirectional"))
    )
    (net (code "141") (name "unconnected-(U$14-Pad37{slash}A18)") (class "Default")
      (node (ref "U$14") (pin "37/A18") (pinfunction "37/A18_37/A18") (pintype "bidirectional"))
    )
    (net (code "142") (name "unconnected-(U$14-Pad38{slash}A19)") (class "Default")
      (node (ref "U$14") (pin "38/A19") (pinfunction "38/A19_38/A19") (pintype "bidirectional"))
    )
    (net (code "143") (name "unconnected-(U$14-PadA10)") (class "Default")
      (node (ref "U$14") (pin "A10") (pinfunction "A10_A10") (pintype "bidirectional"))
    )
    (net (code "144") (name "unconnected-(U$14-PadA11)") (class "Default")
      (node (ref "U$14") (pin "A11") (pinfunction "A11_A11") (pintype "bidirectional"))
    )
    (net (code "145") (name "unconnected-(U$14-PadAREF)") (class "Default")
      (node (ref "U$14") (pin "AREF") (pinfunction "AREF_AREF") (pintype "bidirectional"))
    )
    (net (code "146") (name "unconnected-(U$14-PadGND3)") (class "Default")
      (node (ref "U$14") (pin "GND3") (pinfunction "GND3_GND3") (pintype "bidirectional"))
    )
    (net (code "147") (name "unconnected-(U$14-PadPROG)") (class "Default")
      (node (ref "U$14") (pin "PROG") (pinfunction "PROG_PROG") (pintype "bidirectional"))
    )
    (net (code "148") (name "unconnected-(U$14-PadRESET)") (class "Default")
      (node (ref "U$14") (pin "RESET") (pinfunction "RESET_RESET") (pintype "bidirectional"))
    )
    (net (code "149") (name "unconnected-(U$14-PadU5V)") (class "Default")
      (node (ref "U$14") (pin "U5V") (pinfunction "U5V_U5V") (pintype "bidirectional"))
    )
    (net (code "150") (name "unconnected-(U$14-PadUD+)") (class "Default")
      (node (ref "U$14") (pin "UD+") (pinfunction "UD+_UD+") (pintype "bidirectional"))
    )
    (net (code "151") (name "unconnected-(U$14-PadUD-)") (class "Default")
      (node (ref "U$14") (pin "UD-") (pinfunction "UD-_UD-") (pintype "bidirectional"))
    )
    (net (code "152") (name "unconnected-(U$14-PadUGND1)") (class "Default")
      (node (ref "U$14") (pin "UGND1") (pinfunction "UGND1_UGND1") (pintype "bidirectional"))
    )
    (net (code "153") (name "unconnected-(U$14-PadUGND2)") (class "Default")
      (node (ref "U$14") (pin "UGND2") (pinfunction "UGND2_UGND2") (pintype "bidirectional"))
    )
    (net (code "154") (name "unconnected-(U$14-PadVBAT)") (class "Default")
      (node (ref "U$14") (pin "VBAT") (pinfunction "VBAT_VBAT") (pintype "bidirectional"))
    )
    (net (code "155") (name "unconnected-(U$14-PadVUSB)") (class "Default")
      (node (ref "U$14") (pin "VUSB") (pinfunction "VUSB_VUSB") (pintype "bidirectional"))
    )
    (net (code "156") (name "unconnected-(U$15-DIO0-Pad20)") (class "Default")
      (node (ref "U$15") (pin "20") (pinfunction "DIO0_20") (pintype "bidirectional"))
    )
    (net (code "157") (name "unconnected-(U$15-DIO1-Pad19)") (class "Default")
      (node (ref "U$15") (pin "19") (pinfunction "DIO1_19") (pintype "bidirectional"))
    )
    (net (code "158") (name "unconnected-(U$15-DIO2-Pad18)") (class "Default")
      (node (ref "U$15") (pin "18") (pinfunction "DIO2_18") (pintype "bidirectional"))
    )
    (net (code "159") (name "unconnected-(U$15-DIO3-Pad17)") (class "Default")
      (node (ref "U$15") (pin "17") (pinfunction "DIO3_17") (pintype "bidirectional"))
    )
    (net (code "160") (name "unconnected-(U$15-DIO4-Pad11)") (class "Default")
      (node (ref "U$15") (pin "11") (pinfunction "DIO4_11") (pintype "bidirectional"))
    )
    (net (code "161") (name "unconnected-(U$15-DIO5-Pad15)") (class "Default")
      (node (ref "U$15") (pin "15") (pinfunction "DIO5_15") (pintype "bidirectional"))
    )
    (net (code "162") (name "unconnected-(U$15-DIO9-Pad13)") (class "Default")
      (node (ref "U$15") (pin "13") (pinfunction "DIO9_13") (pintype "bidirectional"))
    )
    (net (code "163") (name "unconnected-(U$15-DIO11-Pad7)") (class "Default")
      (node (ref "U$15") (pin "7") (pinfunction "DIO11_7") (pintype "bidirectional"))
    )
    (net (code "164") (name "unconnected-(U$15-DIO12-Pad4)") (class "Default")
      (node (ref "U$15") (pin "4") (pinfunction "DIO12_4") (pintype "bidirectional"))
    )
    (net (code "165") (name "unconnected-(U$15-DTR-Pad9)") (class "Default")
      (node (ref "U$15") (pin "9") (pinfunction "DTR_9") (pintype "bidirectional"))
    )
    (net (code "166") (name "unconnected-(U$15-RES-Pad8)") (class "Default")
      (node (ref "U$15") (pin "8") (pinfunction "RES_8") (pintype "bidirectional"))
    )
    (net (code "167") (name "unconnected-(U$15-RES-Pad14)") (class "Default")
      (node (ref "U$15") (pin "14") (pinfunction "RES_14") (pintype "bidirectional"))
    )
    (net (code "168") (name "unconnected-(U$15-RSSI-Pad6)") (class "Default")
      (node (ref "U$15") (pin "6") (pinfunction "RSSI_6") (pintype "bidirectional"))
    )
    (net (code "169") (name "unconnected-(U$16-CS_DIS-Pad6)") (class "Default")
      (node (ref "U$16") (pin "6") (pinfunction "CS_DIS_6") (pintype "bidirectional"))
    )
    (net (code "170") (name "unconnected-(U$17-GPA0-Pad21)") (class "Default")
      (node (ref "U$17") (pin "21") (pinfunction "GPA0_21") (pintype "bidirectional"))
    )
    (net (code "171") (name "unconnected-(U$17-GPA1-Pad22)") (class "Default")
      (node (ref "U$17") (pin "22") (pinfunction "GPA1_22") (pintype "bidirectional"))
    )
    (net (code "172") (name "unconnected-(U$17-GPA2-Pad23)") (class "Default")
      (node (ref "U$17") (pin "23") (pinfunction "GPA2_23") (pintype "bidirectional"))
    )
    (net (code "173") (name "unconnected-(U$17-GPA3-Pad24)") (class "Default")
      (node (ref "U$17") (pin "24") (pinfunction "GPA3_24") (pintype "bidirectional"))
    )
    (net (code "174") (name "unconnected-(U$17-GPA4-Pad25)") (class "Default")
      (node (ref "U$17") (pin "25") (pinfunction "GPA4_25") (pintype "bidirectional"))
    )
    (net (code "175") (name "unconnected-(U$17-GPA5-Pad26)") (class "Default")
      (node (ref "U$17") (pin "26") (pinfunction "GPA5_26") (pintype "bidirectional"))
    )
    (net (code "176") (name "unconnected-(U$17-GPA6-Pad27)") (class "Default")
      (node (ref "U$17") (pin "27") (pinfunction "GPA6_27") (pintype "bidirectional"))
    )
    (net (code "177") (name "unconnected-(U$17-GPA7-Pad28)") (class "Default")
      (node (ref "U$17") (pin "28") (pinfunction "GPA7_28") (pintype "bidirectional"))
    )
    (net (code "178") (name "unconnected-(U$17-GPB5-Pad6)") (class "Default")
      (node (ref "U$17") (pin "6") (pinfunction "GPB5_6") (pintype "bidirectional"))
    )
    (net (code "179") (name "unconnected-(U$17-GPB6-Pad7)") (class "Default")
      (node (ref "U$17") (pin "7") (pinfunction "GPB6_7") (pintype "bidirectional"))
    )
    (net (code "180") (name "unconnected-(U$17-GPB7-Pad8)") (class "Default")
      (node (ref "U$17") (pin "8") (pinfunction "GPB7_8") (pintype "bidirectional"))
    )
    (net (code "181") (name "unconnected-(U$17-INTB-Pad19)") (class "Default")
      (node (ref "U$17") (pin "19") (pinfunction "INTB_19") (pintype "bidirectional"))
    )
    (net (code "182") (name "unconnected-(U$17-NC0-Pad11)") (class "Default")
      (node (ref "U$17") (pin "11") (pinfunction "NC0_11") (pintype "bidirectional"))
    )
    (net (code "183") (name "unconnected-(U$17-NC1-Pad14)") (class "Default")
      (node (ref "U$17") (pin "14") (pinfunction "NC1_14") (pintype "bidirectional"))
    )
    (net (code "184") (name "unconnected-(U$18-BAL-Pad5)") (class "Default")
      (node (ref "U$18") (pin "5") (pinfunction "BAL_5") (pintype "bidirectional"))
    )
    (net (code "185") (name "unconnected-(U$18-BAL{slash}STRB-Pad6)") (class "Default")
      (node (ref "U$18") (pin "6") (pinfunction "BAL/STRB_6") (pintype "bidirectional"))
    )
    (net (code "186") (name "unconnected-(U$21-GPA0-Pad21)") (class "Default")
      (node (ref "U$21") (pin "21") (pinfunction "GPA0_21") (pintype "bidirectional"))
    )
    (net (code "187") (name "unconnected-(U$21-GPA1-Pad22)") (class "Default")
      (node (ref "U$21") (pin "22") (pinfunction "GPA1_22") (pintype "bidirectional"))
    )
    (net (code "188") (name "unconnected-(U$21-GPA2-Pad23)") (class "Default")
      (node (ref "U$21") (pin "23") (pinfunction "GPA2_23") (pintype "bidirectional"))
    )
    (net (code "189") (name "unconnected-(U$21-GPB5-Pad6)") (class "Default")
      (node (ref "U$21") (pin "6") (pinfunction "GPB5_6") (pintype "bidirectional"))
    )
    (net (code "190") (name "unconnected-(U$21-GPB6-Pad7)") (class "Default")
      (node (ref "U$21") (pin "7") (pinfunction "GPB6_7") (pintype "bidirectional"))
    )
    (net (code "191") (name "unconnected-(U$21-GPB7-Pad8)") (class "Default")
      (node (ref "U$21") (pin "8") (pinfunction "GPB7_8") (pintype "bidirectional"))
    )
    (net (code "192") (name "unconnected-(U$21-INTB-Pad19)") (class "Default")
      (node (ref "U$21") (pin "19") (pinfunction "INTB_19") (pintype "bidirectional"))
    )
    (net (code "193") (name "unconnected-(U$21-NC0-Pad11)") (class "Default")
      (node (ref "U$21") (pin "11") (pinfunction "NC0_11") (pintype "bidirectional"))
    )
    (net (code "194") (name "unconnected-(U$21-NC1-Pad14)") (class "Default")
      (node (ref "U$21") (pin "14") (pinfunction "NC1_14") (pintype "bidirectional"))
    )
  )
)
